# power_supply_module.net
KiCad netlist of a schematic drawn in EAGLE
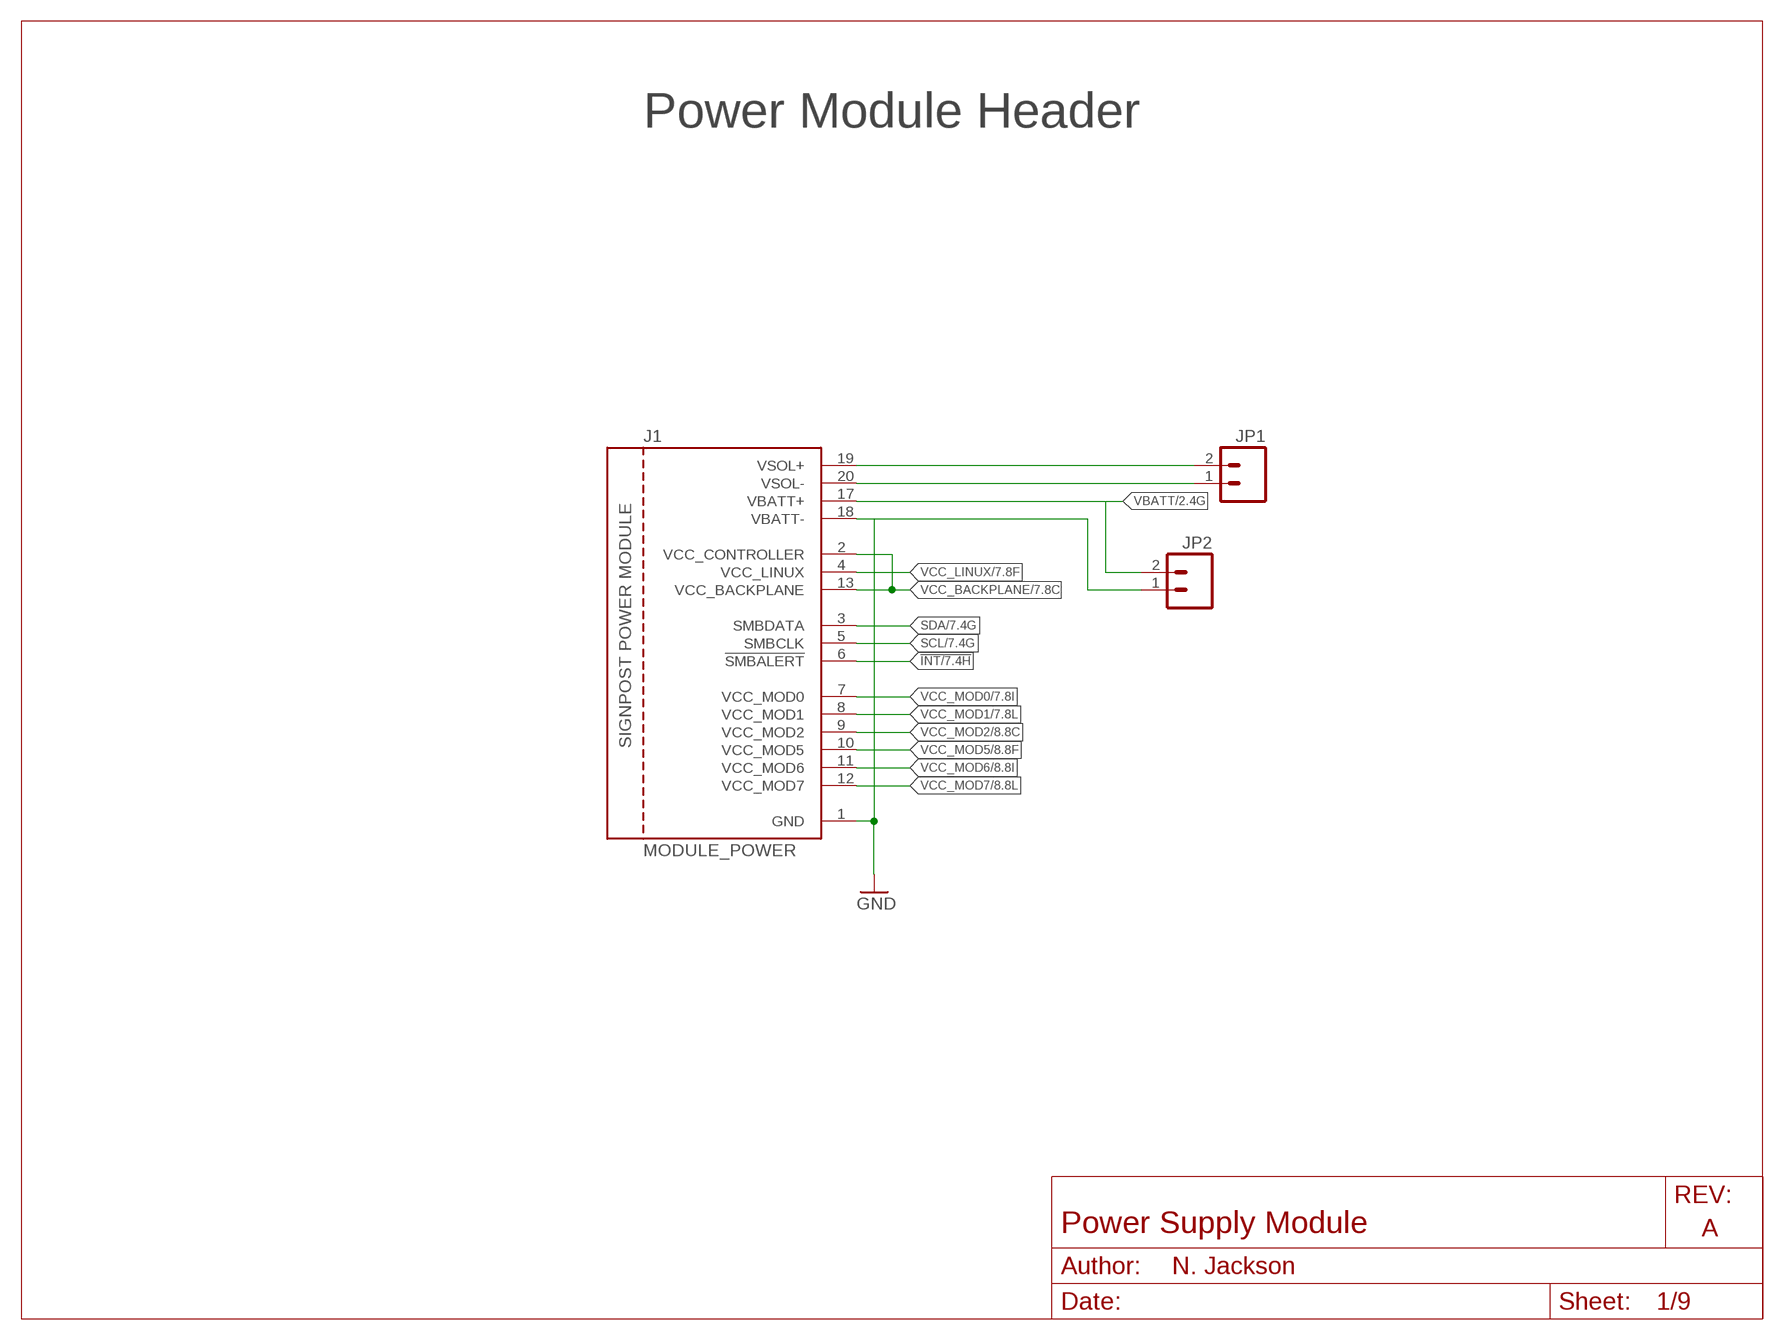
[diagram p0: schematic, sheet 1]
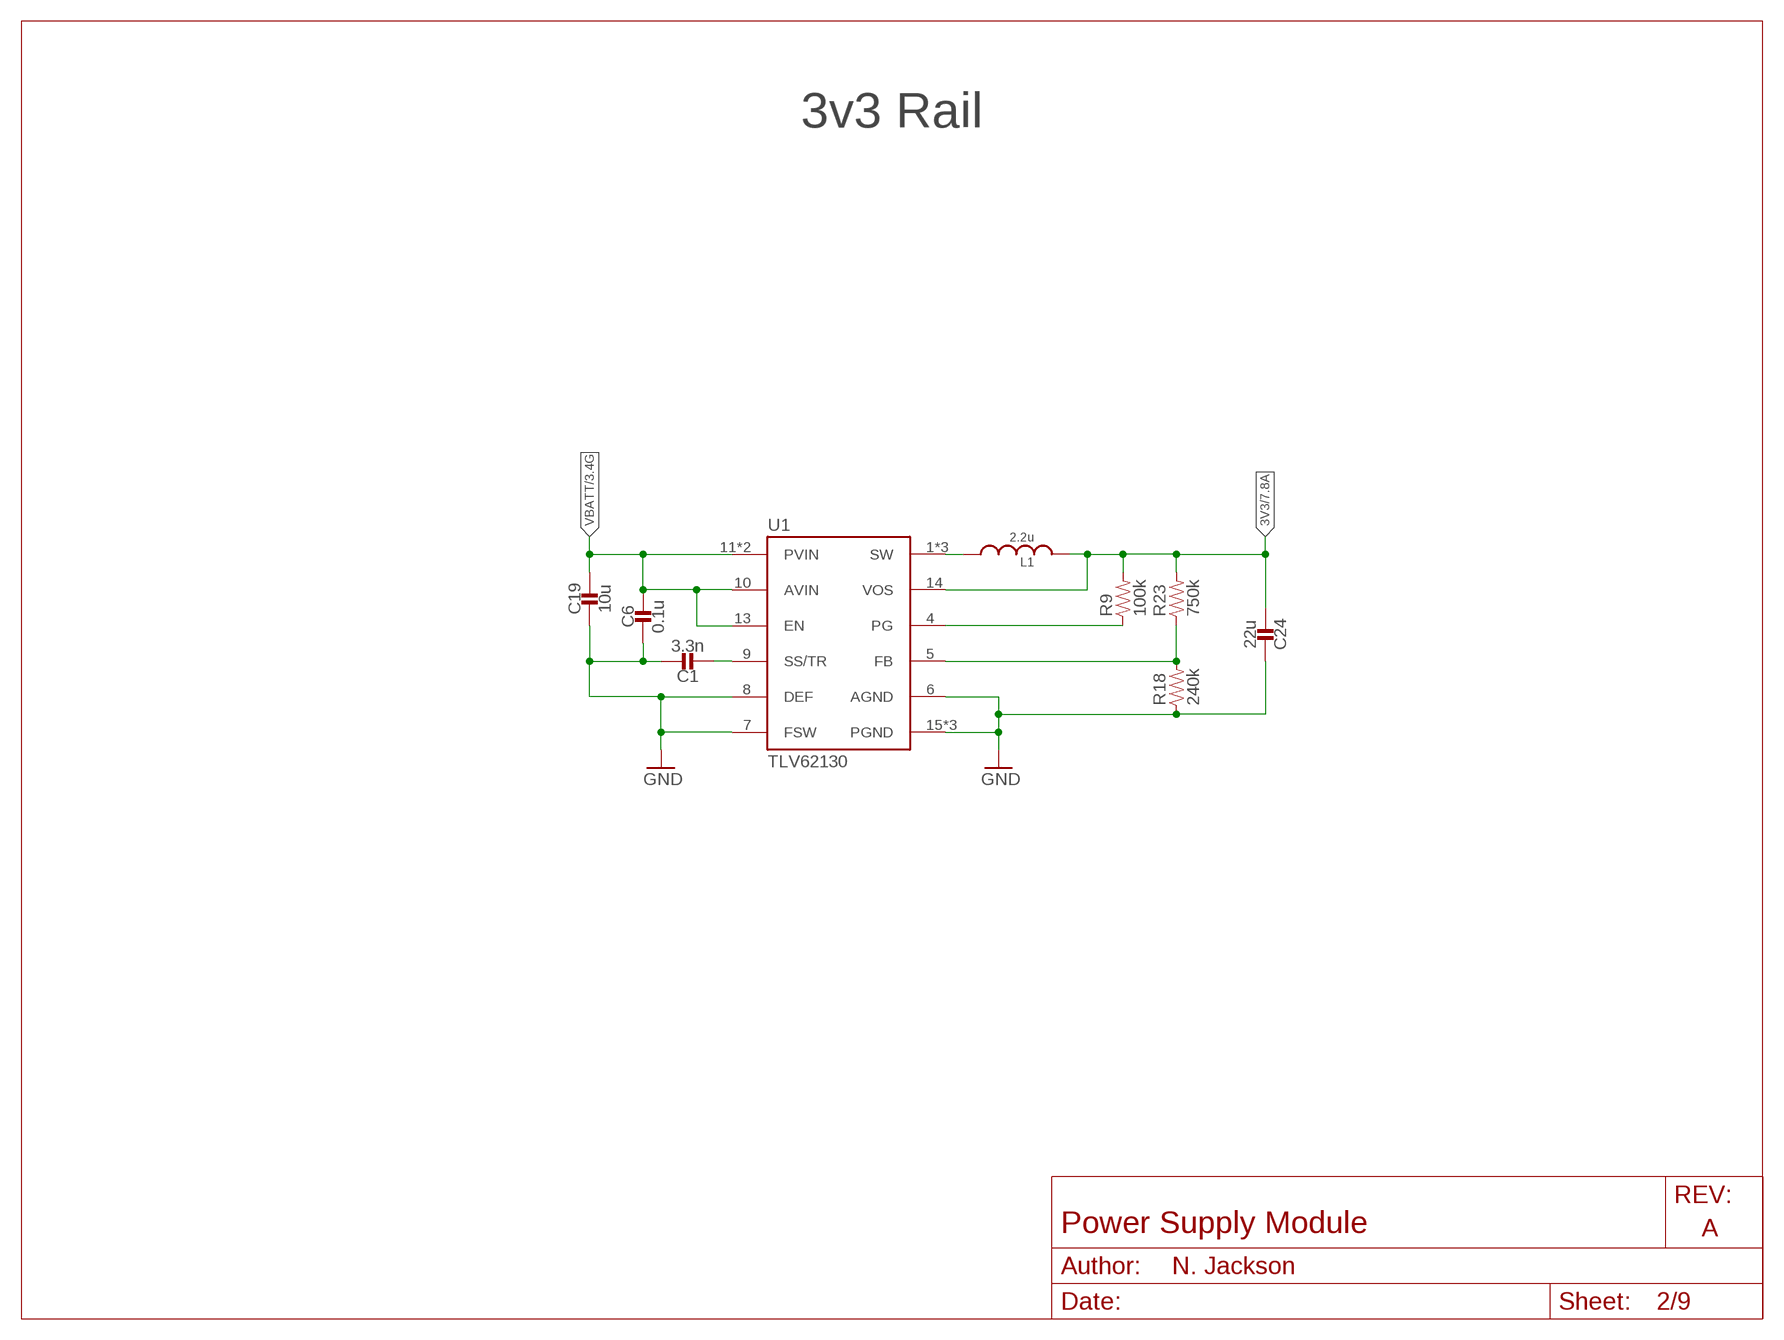
[diagram p1: schematic, sheet 2]
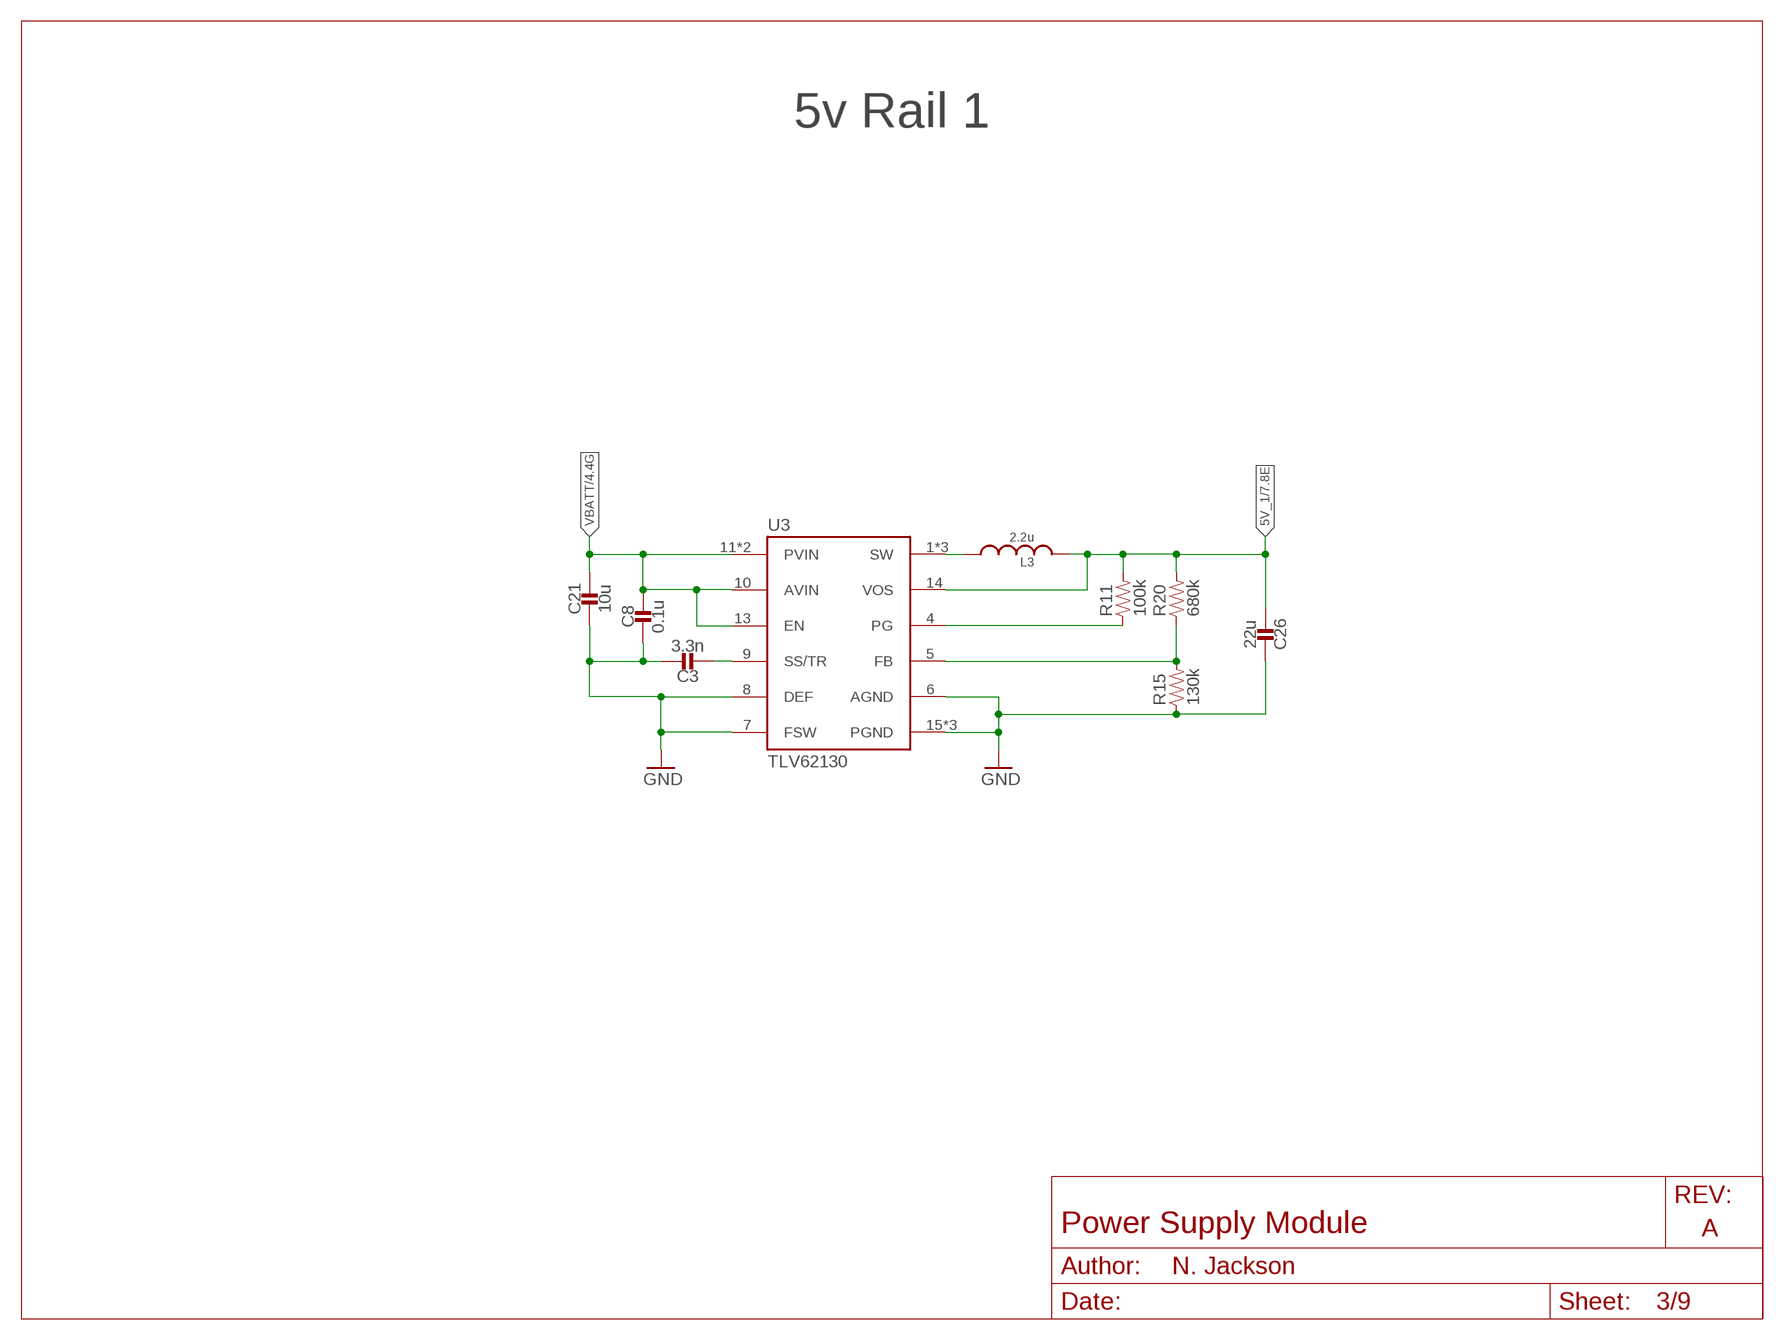
[diagram p2: schematic, sheet 3]
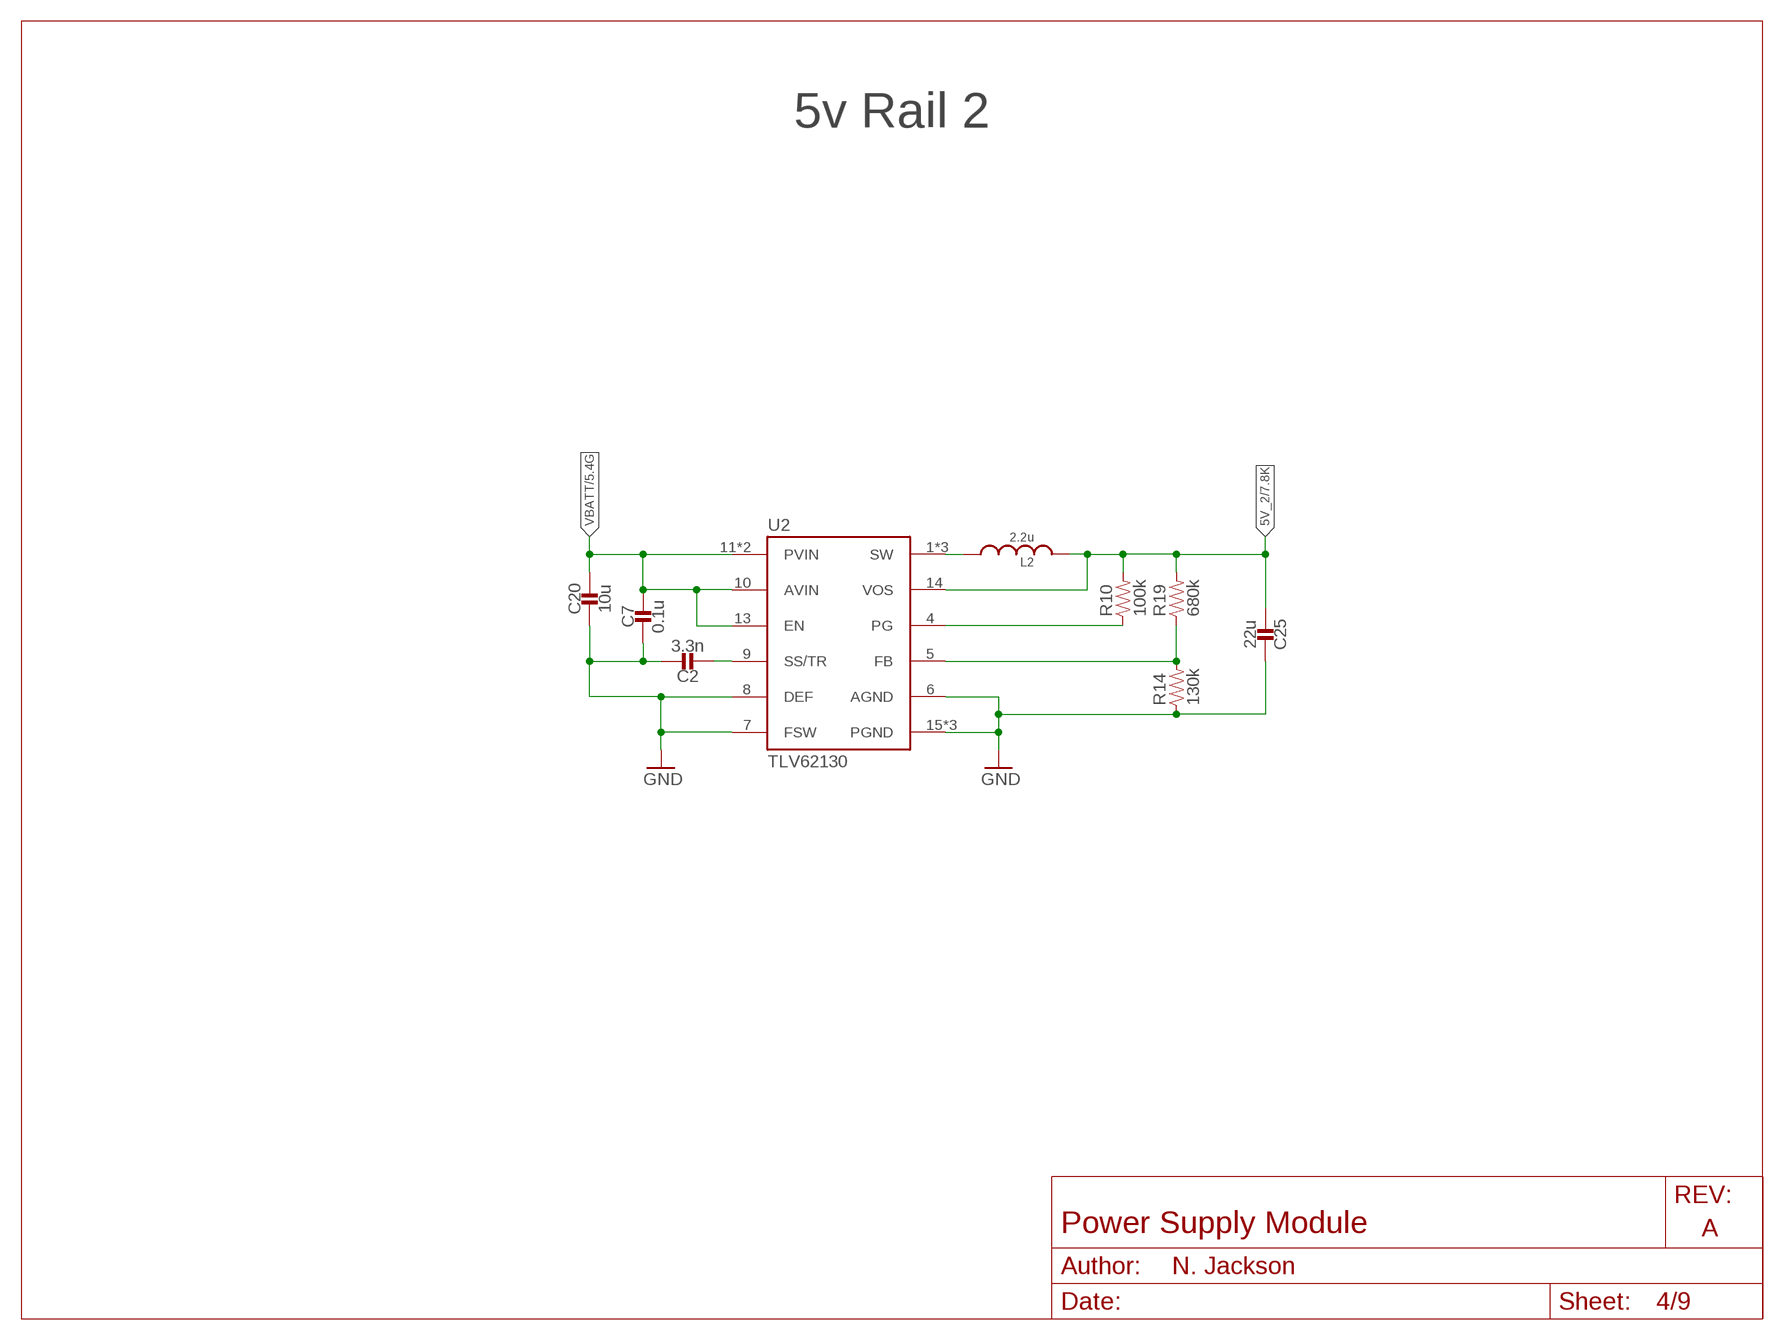
[diagram p3: schematic, sheet 4]
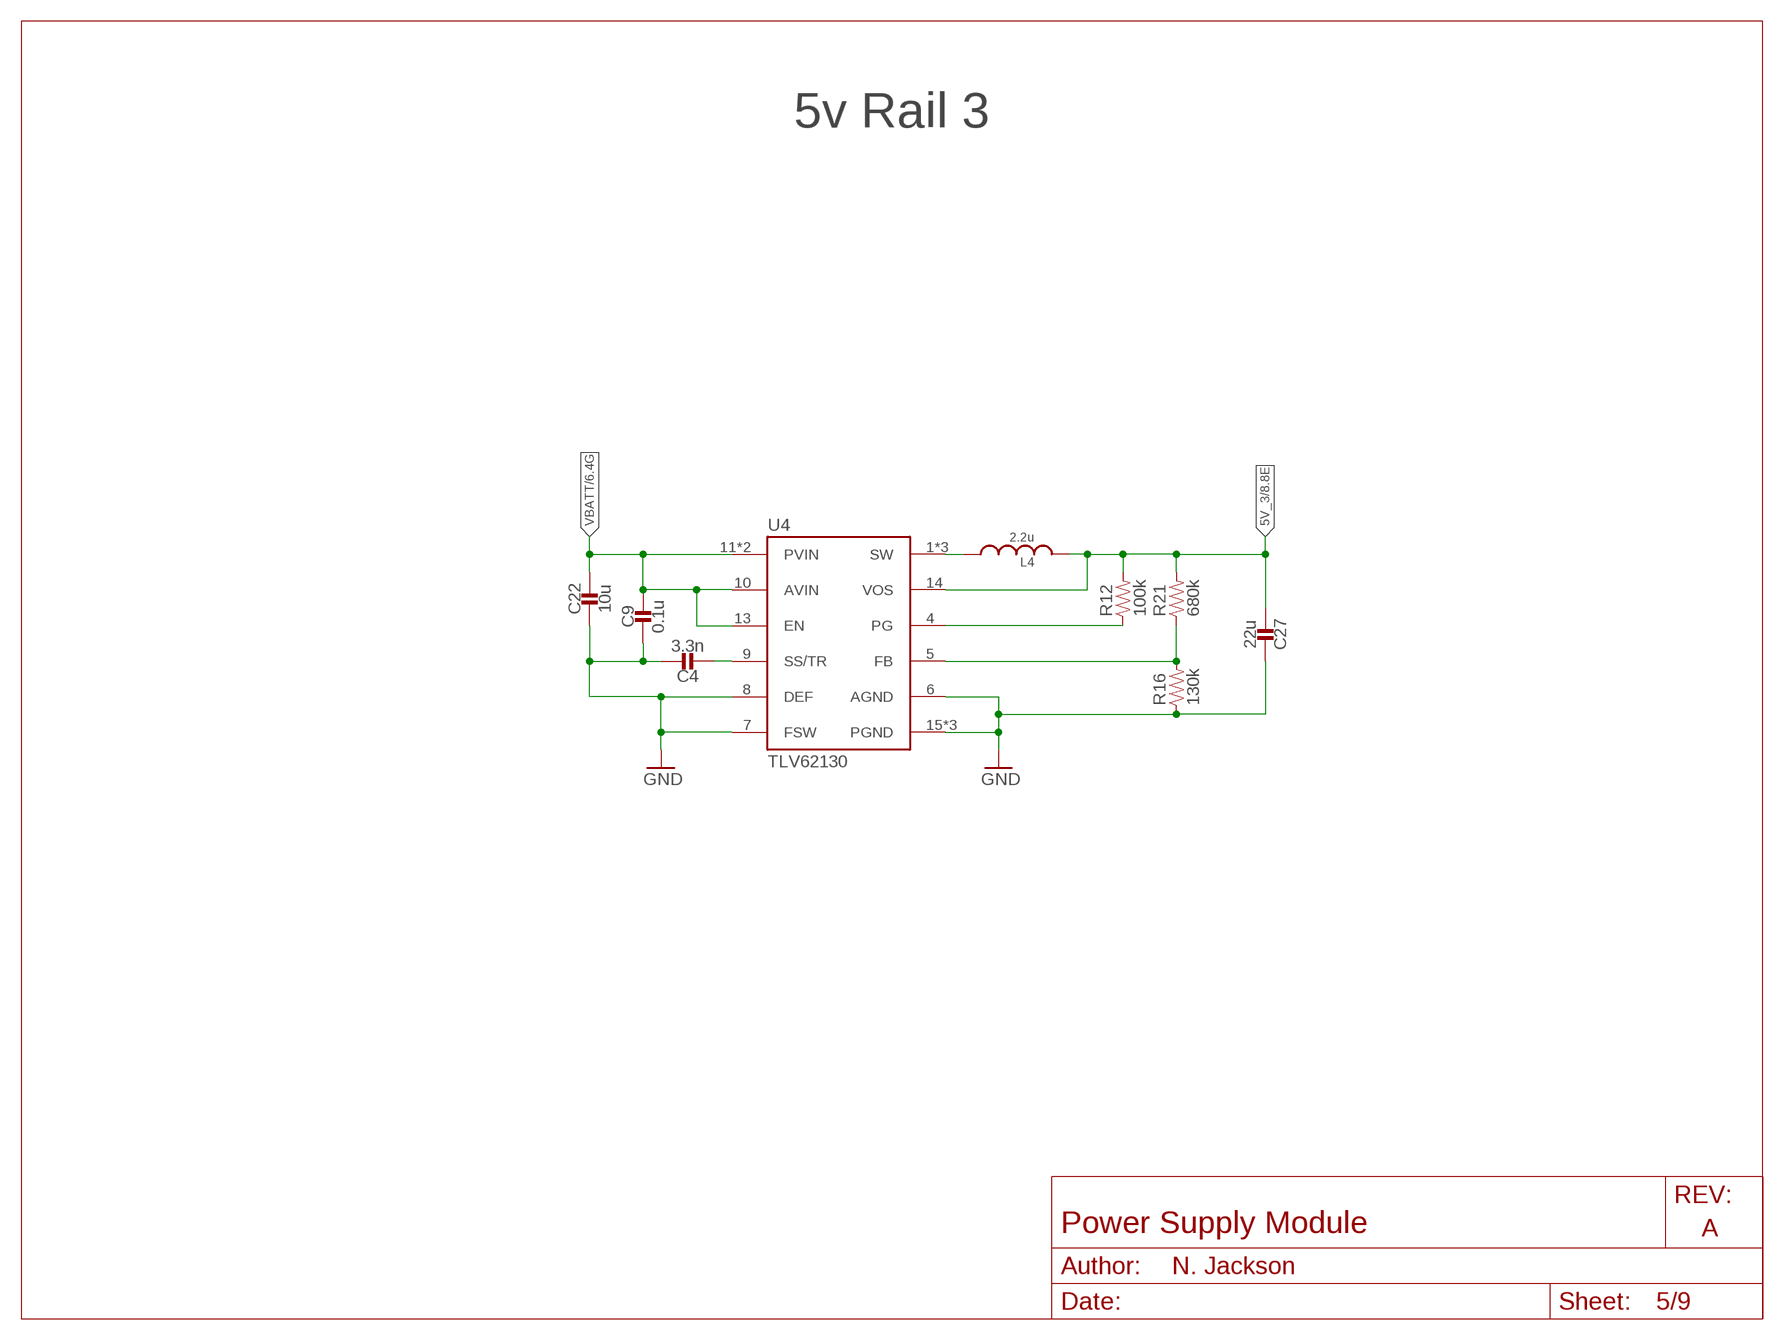
[diagram p4: schematic, sheet 5]
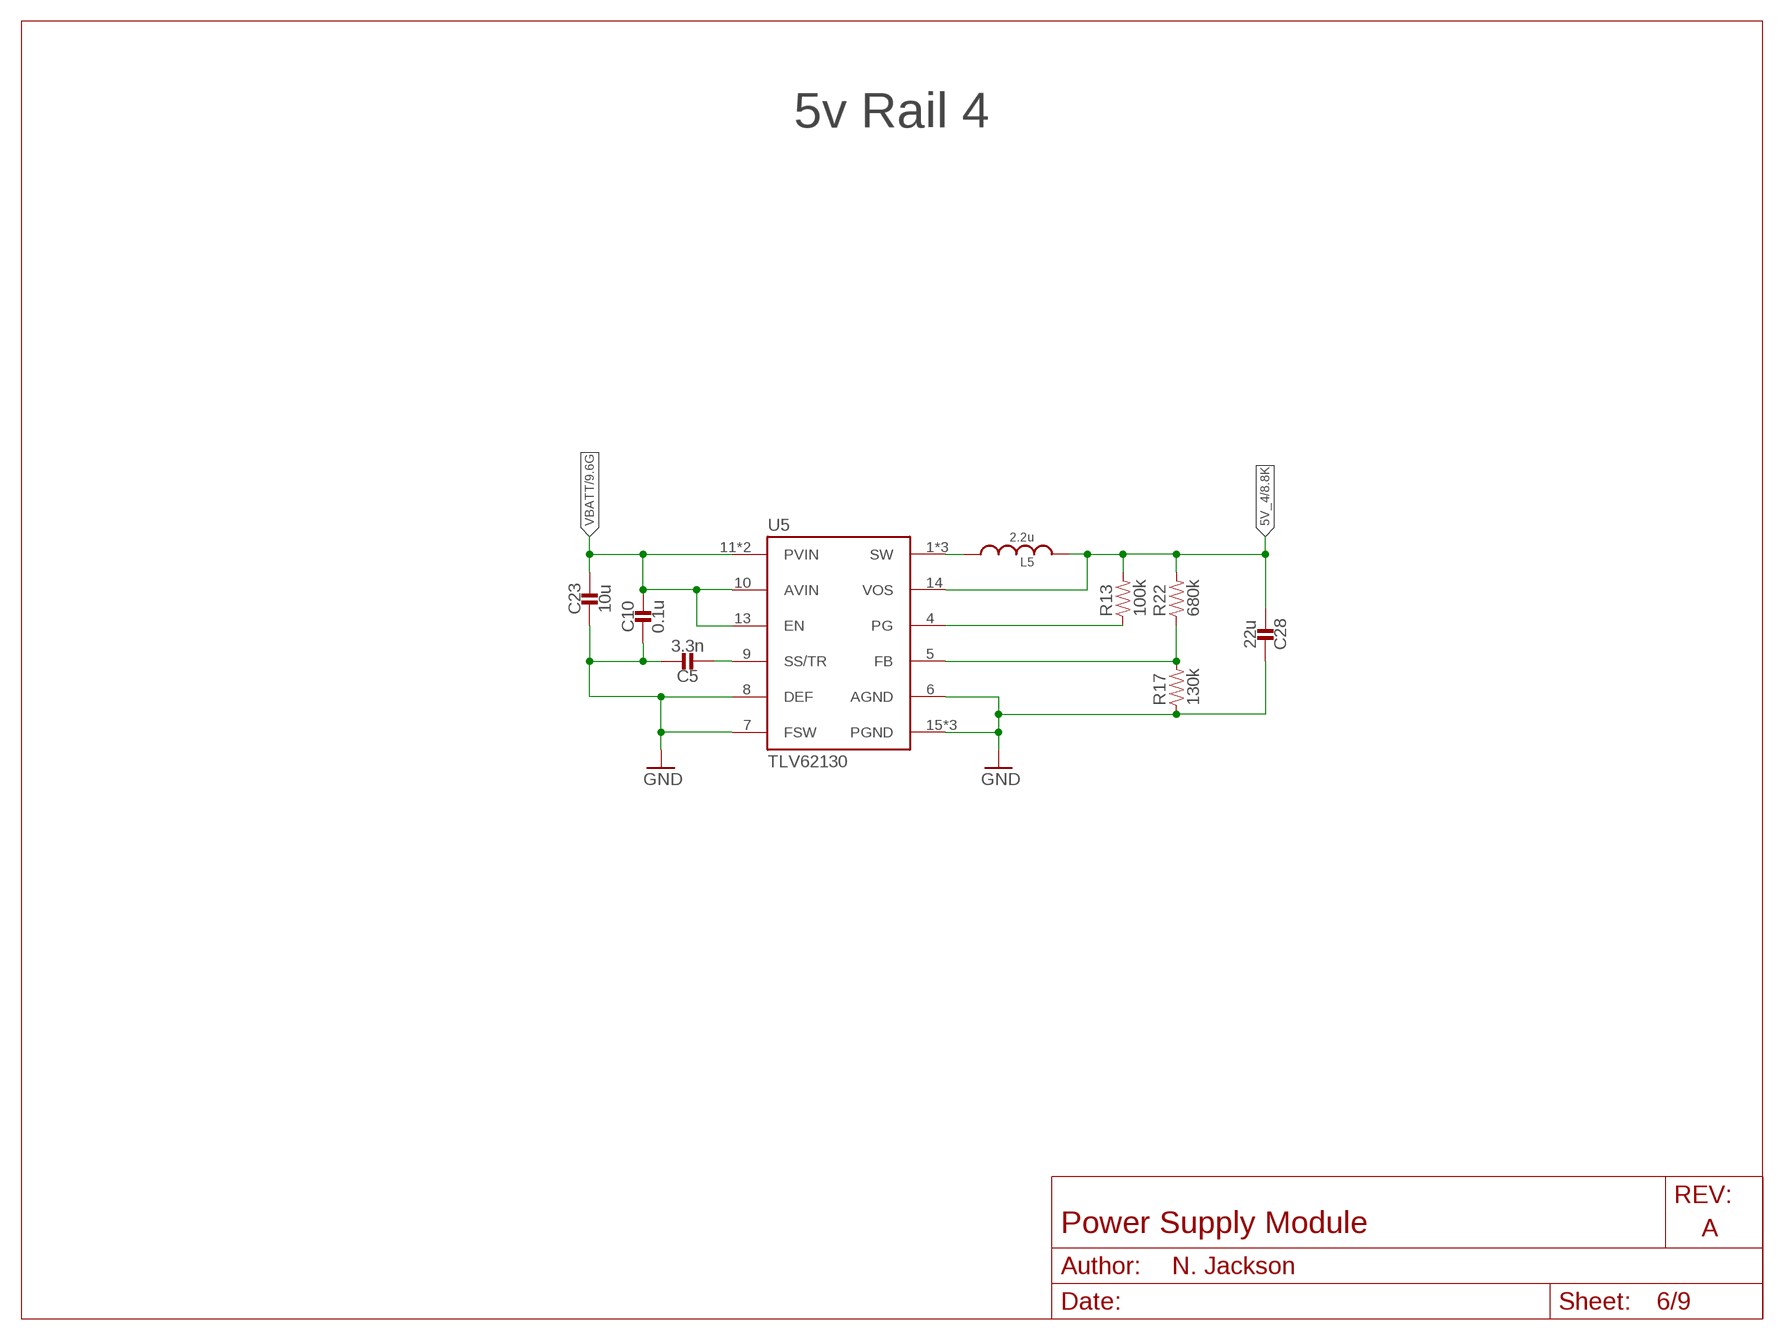
[diagram p5: schematic, sheet 6]
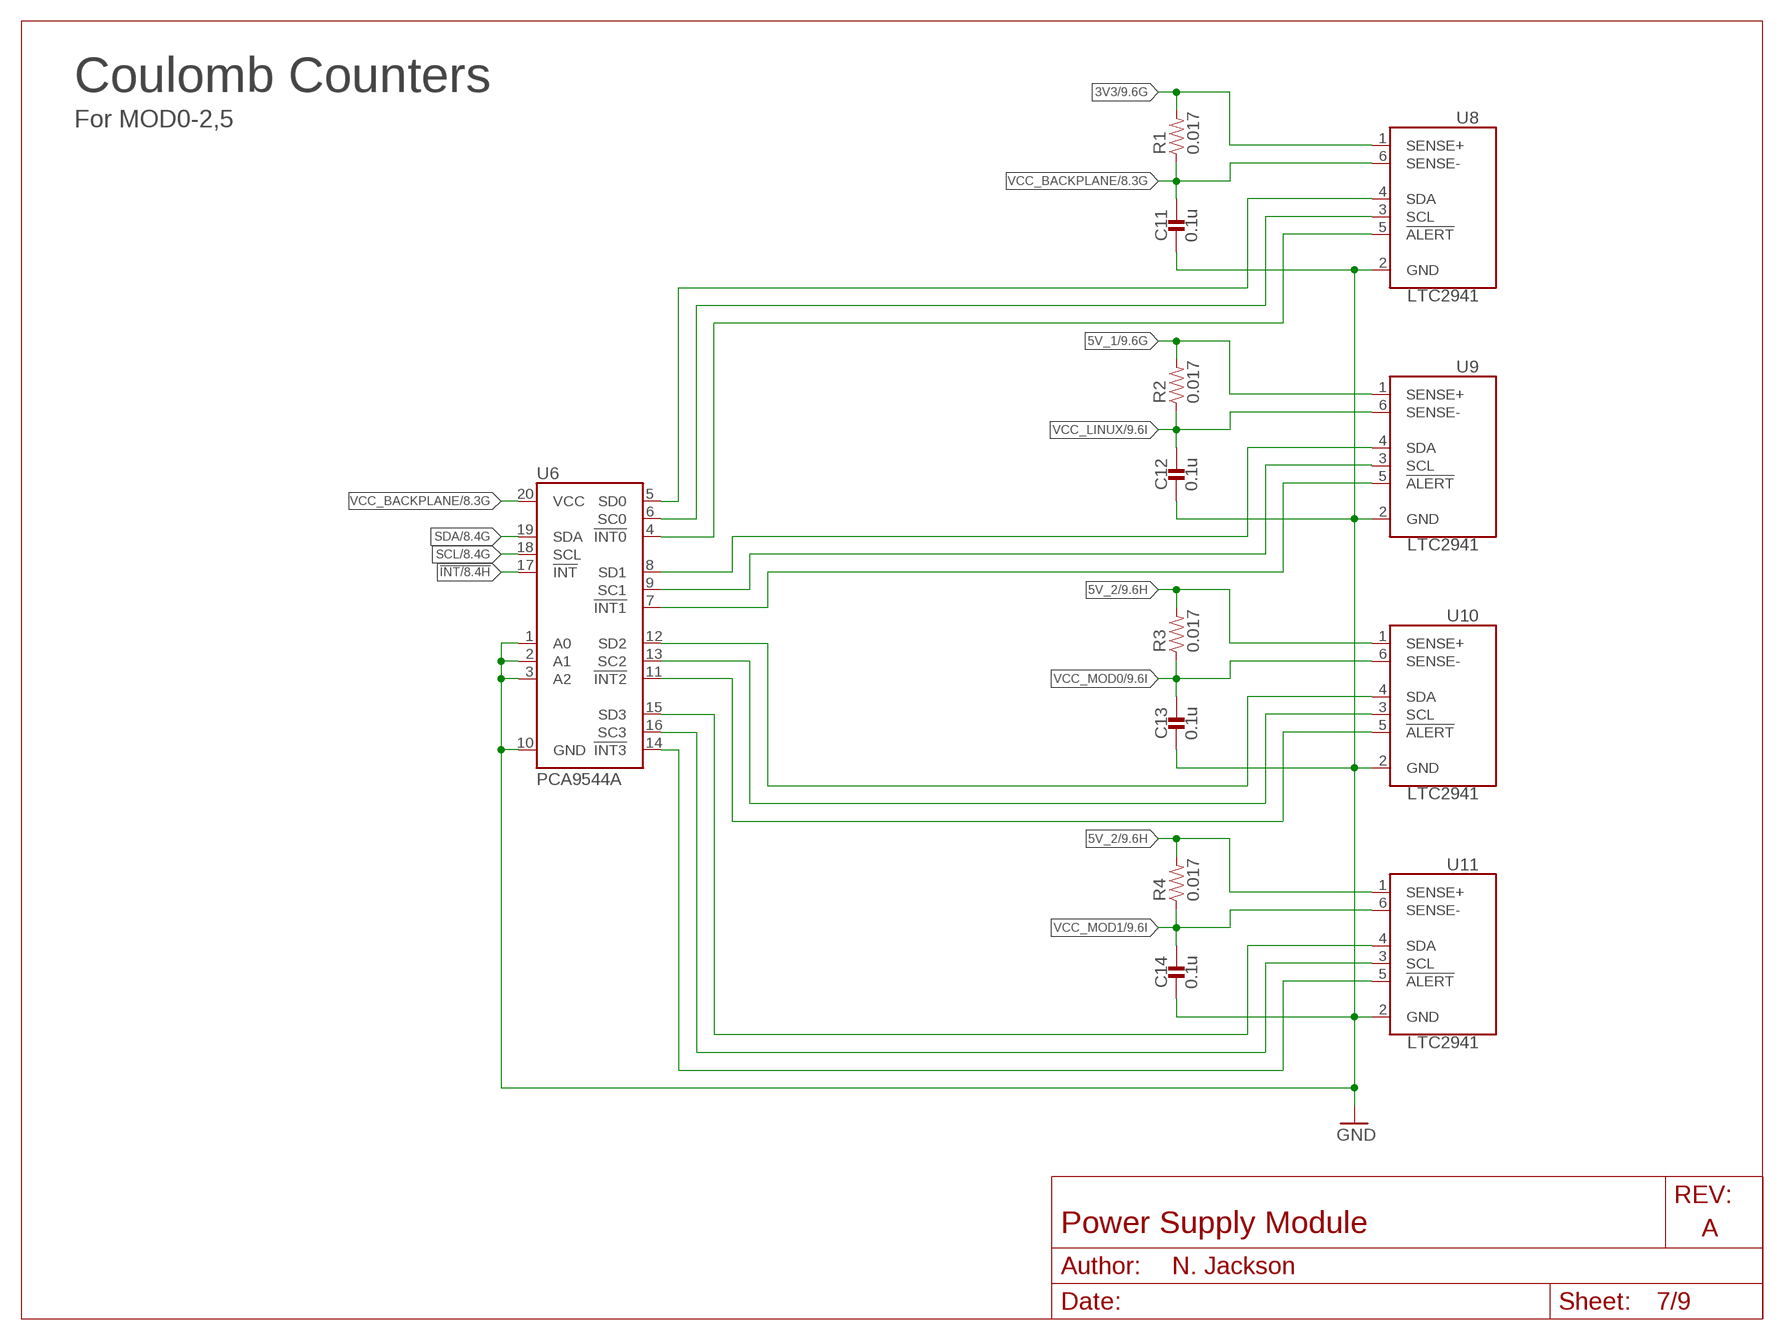
[diagram p6: schematic, sheet 7]
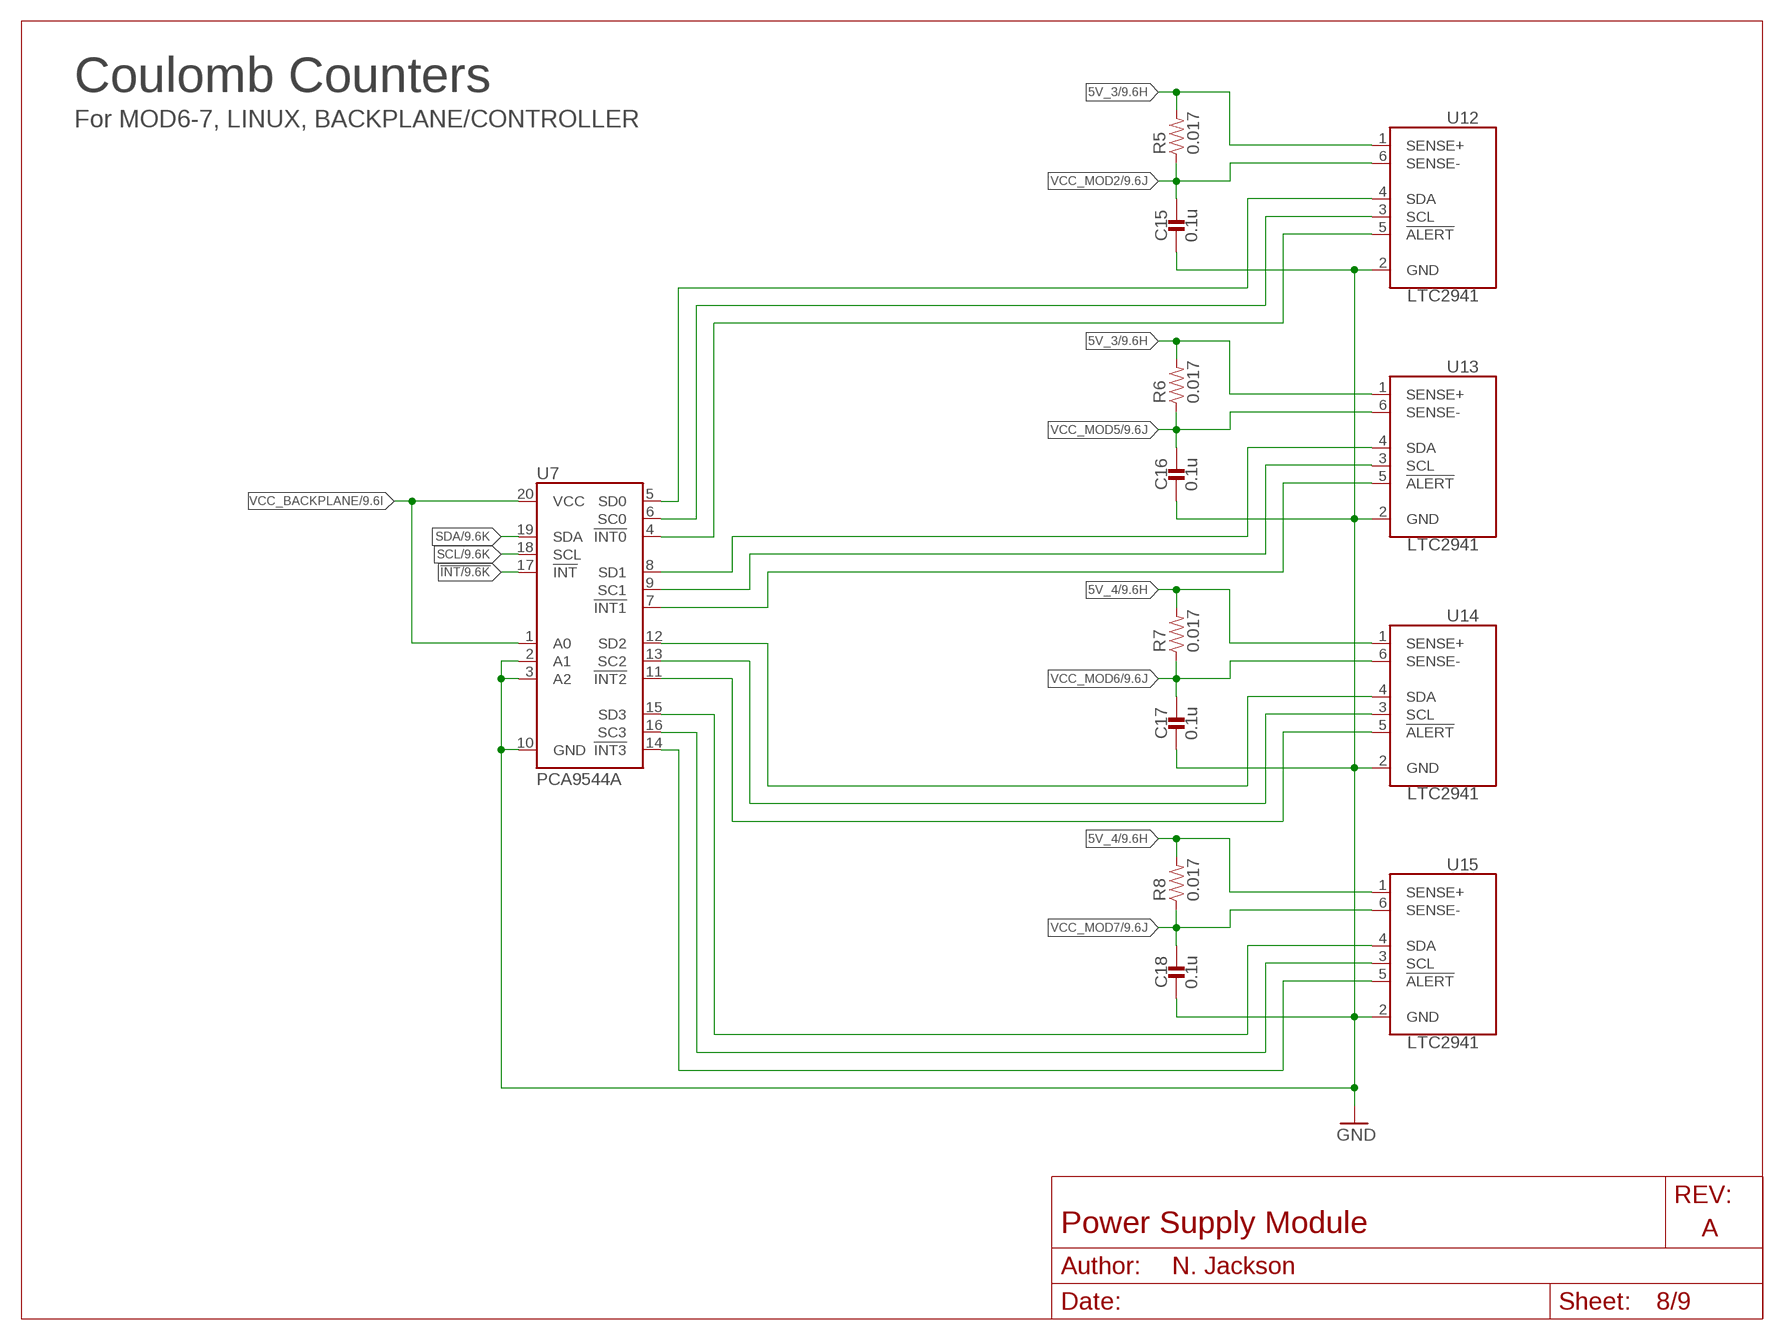
[diagram p7: schematic, sheet 8]
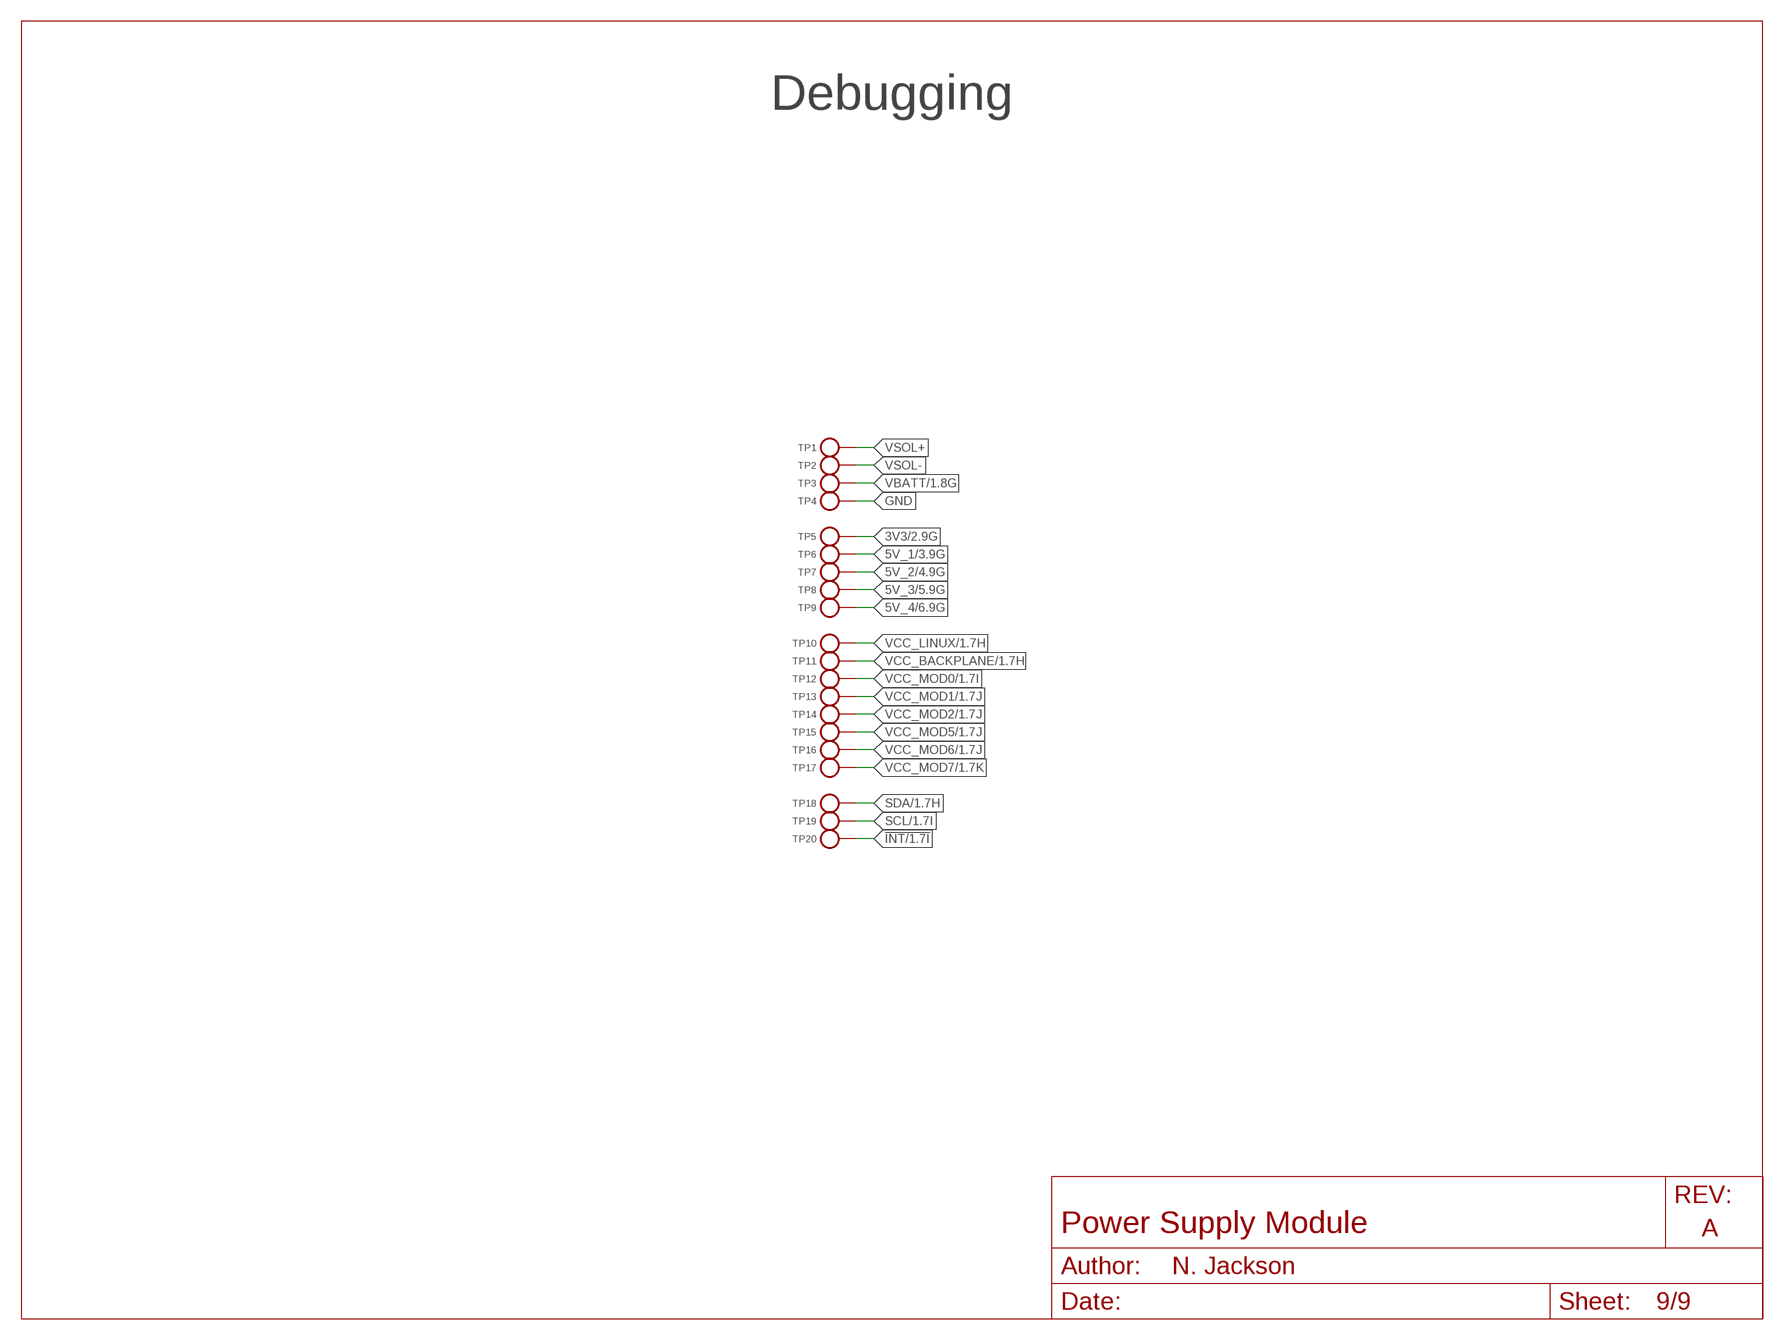
[diagram p8: schematic, sheet 9]

(export (version "E")
  (design (tool "Eeschema 10.0.6"))
  (components
    (comp (ref "C4")
      (value "3.3n")
      (footprint "eagle-import:0402_CAP")
      (libsource (lib "eagle-import") (part "CAPACITOR0402_CAP"))
    )
    (comp (ref "C9")
      (value "0.1u")
      (footprint "eagle-import:0402_CAP")
      (libsource (lib "eagle-import") (part "CAPACITOR0402_CAP"))
    )
    (comp (ref "C22")
      (value "10u")
      (footprint "eagle-import:0805_CAP")
      (libsource (lib "eagle-import") (part "CAPACITOR0805_CAP"))
    )
    (comp (ref "C27")
      (value "22u")
      (footprint "eagle-import:0603_CAP")
      (libsource (lib "eagle-import") (part "CAPACITOR0603_CAP"))
    )
    (comp (ref "L4")
      (value "2.2u")
      (footprint "eagle-import:IHL-1212BZ-11")
      (libsource (lib "eagle-import") (part "INDUCTORIHL"))
    )
    (comp (ref "R12")
      (value "100k")
      (footprint "eagle-import:0402_RES")
      (libsource (lib "eagle-import") (part "RESISTOR0402_RES"))
    )
    (comp (ref "R16")
      (value "130k")
      (footprint "eagle-import:0402_RES")
      (libsource (lib "eagle-import") (part "RESISTOR0402_RES"))
    )
    (comp (ref "R21")
      (value "680k")
      (footprint "eagle-import:0402_RES")
      (libsource (lib "eagle-import") (part "RESISTOR0402_RES"))
    )
    (comp (ref "U4")
      (value "TLV62130")
      (footprint "eagle-import:TQFN-16_3MM")
      (libsource (lib "eagle-import") (part "TLV62130"))
    )
    (comp (ref "C5")
      (value "3.3n")
      (footprint "eagle-import:0402_CAP")
      (libsource (lib "eagle-import") (part "CAPACITOR0402_CAP"))
    )
    (comp (ref "C10")
      (value "0.1u")
      (footprint "eagle-import:0402_CAP")
      (libsource (lib "eagle-import") (part "CAPACITOR0402_CAP"))
    )
    (comp (ref "C23")
      (value "10u")
      (footprint "eagle-import:0805_CAP")
      (libsource (lib "eagle-import") (part "CAPACITOR0805_CAP"))
    )
    (comp (ref "C28")
      (value "22u")
      (footprint "eagle-import:0603_CAP")
      (libsource (lib "eagle-import") (part "CAPACITOR0603_CAP"))
    )
    (comp (ref "L5")
      (value "2.2u")
      (footprint "eagle-import:IHL-1212BZ-11")
      (libsource (lib "eagle-import") (part "INDUCTORIHL"))
    )
    (comp (ref "R13")
      (value "100k")
      (footprint "eagle-import:0402_RES")
      (libsource (lib "eagle-import") (part "RESISTOR0402_RES"))
    )
    (comp (ref "R17")
      (value "130k")
      (footprint "eagle-import:0402_RES")
      (libsource (lib "eagle-import") (part "RESISTOR0402_RES"))
    )
    (comp (ref "R22")
      (value "680k")
      (footprint "eagle-import:0402_RES")
      (libsource (lib "eagle-import") (part "RESISTOR0402_RES"))
    )
    (comp (ref "U5")
      (value "TLV62130")
      (footprint "eagle-import:TQFN-16_3MM")
      (libsource (lib "eagle-import") (part "TLV62130"))
    )
    (comp (ref "TP1")
      (value "TEST_POINT_0.040IN")
      (footprint "eagle-import:TESTPOINT_0.040IN")
      (libsource (lib "eagle-import") (part "TEST_POINT_0.040IN"))
    )
    (comp (ref "TP2")
      (value "TEST_POINT_0.040IN")
      (footprint "eagle-import:TESTPOINT_0.040IN")
      (libsource (lib "eagle-import") (part "TEST_POINT_0.040IN"))
    )
    (comp (ref "TP3")
      (value "TEST_POINT_0.040IN")
      (footprint "eagle-import:TESTPOINT_0.040IN")
      (libsource (lib "eagle-import") (part "TEST_POINT_0.040IN"))
    )
    (comp (ref "TP4")
      (value "TEST_POINT_0.040IN")
      (footprint "eagle-import:TESTPOINT_0.040IN")
      (libsource (lib "eagle-import") (part "TEST_POINT_0.040IN"))
    )
    (comp (ref "TP5")
      (value "TEST_POINT_0.040IN")
      (footprint "eagle-import:TESTPOINT_0.040IN")
      (libsource (lib "eagle-import") (part "TEST_POINT_0.040IN"))
    )
    (comp (ref "TP6")
      (value "TEST_POINT_0.040IN")
      (footprint "eagle-import:TESTPOINT_0.040IN")
      (libsource (lib "eagle-import") (part "TEST_POINT_0.040IN"))
    )
    (comp (ref "TP7")
      (value "TEST_POINT_0.040IN")
      (footprint "eagle-import:TESTPOINT_0.040IN")
      (libsource (lib "eagle-import") (part "TEST_POINT_0.040IN"))
    )
    (comp (ref "TP8")
      (value "TEST_POINT_0.040IN")
      (footprint "eagle-import:TESTPOINT_0.040IN")
      (libsource (lib "eagle-import") (part "TEST_POINT_0.040IN"))
    )
    (comp (ref "TP9")
      (value "TEST_POINT_0.040IN")
      (footprint "eagle-import:TESTPOINT_0.040IN")
      (libsource (lib "eagle-import") (part "TEST_POINT_0.040IN"))
    )
    (comp (ref "TP10")
      (value "TEST_POINT_0.040IN")
      (footprint "eagle-import:TESTPOINT_0.040IN")
      (libsource (lib "eagle-import") (part "TEST_POINT_0.040IN"))
    )
    (comp (ref "TP11")
      (value "TEST_POINT_0.040IN")
      (footprint "eagle-import:TESTPOINT_0.040IN")
      (libsource (lib "eagle-import") (part "TEST_POINT_0.040IN"))
    )
    (comp (ref "TP12")
      (value "TEST_POINT_0.040IN")
      (footprint "eagle-import:TESTPOINT_0.040IN")
      (libsource (lib "eagle-import") (part "TEST_POINT_0.040IN"))
    )
    (comp (ref "TP13")
      (value "TEST_POINT_0.040IN")
      (footprint "eagle-import:TESTPOINT_0.040IN")
      (libsource (lib "eagle-import") (part "TEST_POINT_0.040IN"))
    )
    (comp (ref "TP14")
      (value "TEST_POINT_0.040IN")
      (footprint "eagle-import:TESTPOINT_0.040IN")
      (libsource (lib "eagle-import") (part "TEST_POINT_0.040IN"))
    )
    (comp (ref "TP15")
      (value "TEST_POINT_0.040IN")
      (footprint "eagle-import:TESTPOINT_0.040IN")
      (libsource (lib "eagle-import") (part "TEST_POINT_0.040IN"))
    )
    (comp (ref "TP16")
      (value "TEST_POINT_0.040IN")
      (footprint "eagle-import:TESTPOINT_0.040IN")
      (libsource (lib "eagle-import") (part "TEST_POINT_0.040IN"))
    )
    (comp (ref "TP17")
      (value "TEST_POINT_0.040IN")
      (footprint "eagle-import:TESTPOINT_0.040IN")
      (libsource (lib "eagle-import") (part "TEST_POINT_0.040IN"))
    )
    (comp (ref "TP18")
      (value "TEST_POINT_0.040IN")
      (footprint "eagle-import:TESTPOINT_0.040IN")
      (libsource (lib "eagle-import") (part "TEST_POINT_0.040IN"))
    )
    (comp (ref "TP19")
      (value "TEST_POINT_0.040IN")
      (footprint "eagle-import:TESTPOINT_0.040IN")
      (libsource (lib "eagle-import") (part "TEST_POINT_0.040IN"))
    )
    (comp (ref "TP20")
      (value "TEST_POINT_0.040IN")
      (footprint "eagle-import:TESTPOINT_0.040IN")
      (libsource (lib "eagle-import") (part "TEST_POINT_0.040IN"))
    )
    (comp (ref "C15")
      (value "0.1u")
      (footprint "eagle-import:0402_CAP")
      (libsource (lib "eagle-import") (part "CAPACITOR0402_CAP"))
    )
    (comp (ref "C16")
      (value "0.1u")
      (footprint "eagle-import:0402_CAP")
      (libsource (lib "eagle-import") (part "CAPACITOR0402_CAP"))
    )
    (comp (ref "C17")
      (value "0.1u")
      (footprint "eagle-import:0402_CAP")
      (libsource (lib "eagle-import") (part "CAPACITOR0402_CAP"))
    )
    (comp (ref "C18")
      (value "0.1u")
      (footprint "eagle-import:0402_CAP")
      (libsource (lib "eagle-import") (part "CAPACITOR0402_CAP"))
    )
    (comp (ref "R5")
      (value "0.017")
      (footprint "eagle-import:0805_RES")
      (libsource (lib "eagle-import") (part "RESISTOR0805_RES"))
    )
    (comp (ref "R6")
      (value "0.017")
      (footprint "eagle-import:0805_RES")
      (libsource (lib "eagle-import") (part "RESISTOR0805_RES"))
    )
    (comp (ref "R7")
      (value "0.017")
      (footprint "eagle-import:0805_RES")
      (libsource (lib "eagle-import") (part "RESISTOR0805_RES"))
    )
    (comp (ref "R8")
      (value "0.017")
      (footprint "eagle-import:0805_RES")
      (libsource (lib "eagle-import") (part "RESISTOR0805_RES"))
    )
    (comp (ref "U7")
      (value "PCA9544A")
      (footprint "eagle-import:SO20L")
      (libsource (lib "eagle-import") (part "PCA9544A"))
    )
    (comp (ref "U12")
      (value "LTC2941")
      (footprint "eagle-import:DFN-6-2MMX3MM")
      (libsource (lib "eagle-import") (part "LTC2941"))
    )
    (comp (ref "U13")
      (value "LTC2941")
      (footprint "eagle-import:DFN-6-2MMX3MM")
      (libsource (lib "eagle-import") (part "LTC2941"))
    )
    (comp (ref "U14")
      (value "LTC2941")
      (footprint "eagle-import:DFN-6-2MMX3MM")
      (libsource (lib "eagle-import") (part "LTC2941"))
    )
    (comp (ref "U15")
      (value "LTC2941")
      (footprint "eagle-import:DFN-6-2MMX3MM")
      (libsource (lib "eagle-import") (part "LTC2941"))
    )
    (comp (ref "C11")
      (value "0.1u")
      (footprint "eagle-import:0402_CAP")
      (libsource (lib "eagle-import") (part "CAPACITOR0402_CAP"))
    )
    (comp (ref "C12")
      (value "0.1u")
      (footprint "eagle-import:0402_CAP")
      (libsource (lib "eagle-import") (part "CAPACITOR0402_CAP"))
    )
    (comp (ref "C13")
      (value "0.1u")
      (footprint "eagle-import:0402_CAP")
      (libsource (lib "eagle-import") (part "CAPACITOR0402_CAP"))
    )
    (comp (ref "C14")
      (value "0.1u")
      (footprint "eagle-import:0402_CAP")
      (libsource (lib "eagle-import") (part "CAPACITOR0402_CAP"))
    )
    (comp (ref "R1")
      (value "0.017")
      (footprint "eagle-import:0805_RES")
      (libsource (lib "eagle-import") (part "RESISTOR0805_RES"))
    )
    (comp (ref "R2")
      (value "0.017")
      (footprint "eagle-import:0805_RES")
      (libsource (lib "eagle-import") (part "RESISTOR0805_RES"))
    )
    (comp (ref "R3")
      (value "0.017")
      (footprint "eagle-import:0805_RES")
      (libsource (lib "eagle-import") (part "RESISTOR0805_RES"))
    )
    (comp (ref "R4")
      (value "0.017")
      (footprint "eagle-import:0805_RES")
      (libsource (lib "eagle-import") (part "RESISTOR0805_RES"))
    )
    (comp (ref "U6")
      (value "PCA9544A")
      (footprint "eagle-import:SO20L")
      (libsource (lib "eagle-import") (part "PCA9544A"))
    )
    (comp (ref "U8")
      (value "LTC2941")
      (footprint "eagle-import:DFN-6-2MMX3MM")
      (libsource (lib "eagle-import") (part "LTC2941"))
    )
    (comp (ref "U9")
      (value "LTC2941")
      (footprint "eagle-import:DFN-6-2MMX3MM")
      (libsource (lib "eagle-import") (part "LTC2941"))
    )
    (comp (ref "U10")
      (value "LTC2941")
      (footprint "eagle-import:DFN-6-2MMX3MM")
      (libsource (lib "eagle-import") (part "LTC2941"))
    )
    (comp (ref "U11")
      (value "LTC2941")
      (footprint "eagle-import:DFN-6-2MMX3MM")
      (libsource (lib "eagle-import") (part "LTC2941"))
    )
    (comp (ref "C2")
      (value "3.3n")
      (footprint "eagle-import:0402_CAP")
      (libsource (lib "eagle-import") (part "CAPACITOR0402_CAP"))
    )
    (comp (ref "C7")
      (value "0.1u")
      (footprint "eagle-import:0402_CAP")
      (libsource (lib "eagle-import") (part "CAPACITOR0402_CAP"))
    )
    (comp (ref "C20")
      (value "10u")
      (footprint "eagle-import:0805_CAP")
      (libsource (lib "eagle-import") (part "CAPACITOR0805_CAP"))
    )
    (comp (ref "C25")
      (value "22u")
      (footprint "eagle-import:0603_CAP")
      (libsource (lib "eagle-import") (part "CAPACITOR0603_CAP"))
    )
    (comp (ref "L2")
      (value "2.2u")
      (footprint "eagle-import:IHL-1212BZ-11")
      (libsource (lib "eagle-import") (part "INDUCTORIHL"))
    )
    (comp (ref "R10")
      (value "100k")
      (footprint "eagle-import:0402_RES")
      (libsource (lib "eagle-import") (part "RESISTOR0402_RES"))
    )
    (comp (ref "R14")
      (value "130k")
      (footprint "eagle-import:0402_RES")
      (libsource (lib "eagle-import") (part "RESISTOR0402_RES"))
    )
    (comp (ref "R19")
      (value "680k")
      (footprint "eagle-import:0402_RES")
      (libsource (lib "eagle-import") (part "RESISTOR0402_RES"))
    )
    (comp (ref "U2")
      (value "TLV62130")
      (footprint "eagle-import:TQFN-16_3MM")
      (libsource (lib "eagle-import") (part "TLV62130"))
    )
    (comp (ref "C1")
      (value "3.3n")
      (footprint "eagle-import:0402_CAP")
      (libsource (lib "eagle-import") (part "CAPACITOR0402_CAP"))
    )
    (comp (ref "C6")
      (value "0.1u")
      (footprint "eagle-import:0402_CAP")
      (libsource (lib "eagle-import") (part "CAPACITOR0402_CAP"))
    )
    (comp (ref "C19")
      (value "10u")
      (footprint "eagle-import:0805_CAP")
      (libsource (lib "eagle-import") (part "CAPACITOR0805_CAP"))
    )
    (comp (ref "C24")
      (value "22u")
      (footprint "eagle-import:0603_CAP")
      (libsource (lib "eagle-import") (part "CAPACITOR0603_CAP"))
    )
    (comp (ref "L1")
      (value "2.2u")
      (footprint "eagle-import:IHL-1212BZ-11")
      (libsource (lib "eagle-import") (part "INDUCTORIHL"))
    )
    (comp (ref "R9")
      (value "100k")
      (footprint "eagle-import:0402_RES")
      (libsource (lib "eagle-import") (part "RESISTOR0402_RES"))
    )
    (comp (ref "R18")
      (value "240k")
      (footprint "eagle-import:0402_RES")
      (libsource (lib "eagle-import") (part "RESISTOR0402_RES"))
    )
    (comp (ref "R23")
      (value "750k")
      (footprint "eagle-import:0402_RES")
      (libsource (lib "eagle-import") (part "RESISTOR0402_RES"))
    )
    (comp (ref "U1")
      (value "TLV62130")
      (footprint "eagle-import:TQFN-16_3MM")
      (libsource (lib "eagle-import") (part "TLV62130"))
    )
    (comp (ref "C3")
      (value "3.3n")
      (footprint "eagle-import:0402_CAP")
      (libsource (lib "eagle-import") (part "CAPACITOR0402_CAP"))
    )
    (comp (ref "C8")
      (value "0.1u")
      (footprint "eagle-import:0402_CAP")
      (libsource (lib "eagle-import") (part "CAPACITOR0402_CAP"))
    )
    (comp (ref "C21")
      (value "10u")
      (footprint "eagle-import:0805_CAP")
      (libsource (lib "eagle-import") (part "CAPACITOR0805_CAP"))
    )
    (comp (ref "C26")
      (value "22u")
      (footprint "eagle-import:0603_CAP")
      (libsource (lib "eagle-import") (part "CAPACITOR0603_CAP"))
    )
    (comp (ref "L3")
      (value "2.2u")
      (footprint "eagle-import:IHL-1212BZ-11")
      (libsource (lib "eagle-import") (part "INDUCTORIHL"))
    )
    (comp (ref "R11")
      (value "100k")
      (footprint "eagle-import:0402_RES")
      (libsource (lib "eagle-import") (part "RESISTOR0402_RES"))
    )
    (comp (ref "R15")
      (value "130k")
      (footprint "eagle-import:0402_RES")
      (libsource (lib "eagle-import") (part "RESISTOR0402_RES"))
    )
    (comp (ref "R20")
      (value "680k")
      (footprint "eagle-import:0402_RES")
      (libsource (lib "eagle-import") (part "RESISTOR0402_RES"))
    )
    (comp (ref "U3")
      (value "TLV62130")
      (footprint "eagle-import:TQFN-16_3MM")
      (libsource (lib "eagle-import") (part "TLV62130"))
    )
    (comp (ref "J1")
      (value "MODULE_POWER")
      (footprint "eagle-import:MODULE_POWER")
      (libsource (lib "eagle-import") (part "MODULE_POWER"))
    )
    (comp (ref "JP1")
      (value "M02PTH")
      (footprint "eagle-import:1X02")
      (libsource (lib "eagle-import") (part "M02PTH"))
    )
    (comp (ref "JP2")
      (value "M02PTH")
      (footprint "eagle-import:1X02")
      (libsource (lib "eagle-import") (part "M02PTH"))
    )
  )
  (nets
    (net (code "1") (name "3V3") (class "Default")
      (node (ref "C24") (pin "2") (pinfunction "2_2") (pintype "bidirectional"))
      (node (ref "L1") (pin "P$2") (pinfunction "2_P$2") (pintype "bidirectional"))
      (node (ref "R1") (pin "2") (pinfunction "2_2") (pintype "passive"))
      (node (ref "R23") (pin "2") (pinfunction "2_2") (pintype "passive"))
      (node (ref "R9") (pin "2") (pinfunction "2_2") (pintype "passive"))
      (node (ref "TP5") (pin "TESTPOINT") (pinfunction "TESTPOINT_TESTPOINT") (pintype "bidirectional"))
      (node (ref "U1") (pin "14") (pinfunction "VOS_14") (pintype "bidirectional"))
      (node (ref "U8") (pin "1") (pinfunction "SENSE+_1") (pintype "open_collector"))
    )
    (net (code "2") (name "5V_1") (class "Default")
      (node (ref "C26") (pin "2") (pinfunction "2_2") (pintype "bidirectional"))
      (node (ref "L3") (pin "P$2") (pinfunction "2_P$2") (pintype "bidirectional"))
      (node (ref "R11") (pin "2") (pinfunction "2_2") (pintype "passive"))
      (node (ref "R2") (pin "2") (pinfunction "2_2") (pintype "passive"))
      (node (ref "R20") (pin "2") (pinfunction "2_2") (pintype "passive"))
      (node (ref "TP6") (pin "TESTPOINT") (pinfunction "TESTPOINT_TESTPOINT") (pintype "bidirectional"))
      (node (ref "U3") (pin "14") (pinfunction "VOS_14") (pintype "bidirectional"))
      (node (ref "U9") (pin "1") (pinfunction "SENSE+_1") (pintype "open_collector"))
    )
    (net (code "3") (name "5V_2") (class "Default")
      (node (ref "C25") (pin "2") (pinfunction "2_2") (pintype "bidirectional"))
      (node (ref "L2") (pin "P$2") (pinfunction "2_P$2") (pintype "bidirectional"))
      (node (ref "R10") (pin "2") (pinfunction "2_2") (pintype "passive"))
      (node (ref "R19") (pin "2") (pinfunction "2_2") (pintype "passive"))
      (node (ref "R3") (pin "2") (pinfunction "2_2") (pintype "passive"))
      (node (ref "R4") (pin "2") (pinfunction "2_2") (pintype "passive"))
      (node (ref "TP7") (pin "TESTPOINT") (pinfunction "TESTPOINT_TESTPOINT") (pintype "bidirectional"))
      (node (ref "U10") (pin "1") (pinfunction "SENSE+_1") (pintype "open_collector"))
      (node (ref "U11") (pin "1") (pinfunction "SENSE+_1") (pintype "open_collector"))
      (node (ref "U2") (pin "14") (pinfunction "VOS_14") (pintype "bidirectional"))
    )
    (net (code "4") (name "5V_3") (class "Default")
      (node (ref "C27") (pin "2") (pinfunction "2_2") (pintype "bidirectional"))
      (node (ref "L4") (pin "P$2") (pinfunction "2_P$2") (pintype "bidirectional"))
      (node (ref "R12") (pin "2") (pinfunction "2_2") (pintype "passive"))
      (node (ref "R21") (pin "2") (pinfunction "2_2") (pintype "passive"))
      (node (ref "R5") (pin "2") (pinfunction "2_2") (pintype "passive"))
      (node (ref "R6") (pin "2") (pinfunction "2_2") (pintype "passive"))
      (node (ref "TP8") (pin "TESTPOINT") (pinfunction "TESTPOINT_TESTPOINT") (pintype "bidirectional"))
      (node (ref "U12") (pin "1") (pinfunction "SENSE+_1") (pintype "open_collector"))
      (node (ref "U13") (pin "1") (pinfunction "SENSE+_1") (pintype "open_collector"))
      (node (ref "U4") (pin "14") (pinfunction "VOS_14") (pintype "bidirectional"))
    )
    (net (code "5") (name "5V_4") (class "Default")
      (node (ref "C28") (pin "2") (pinfunction "2_2") (pintype "bidirectional"))
      (node (ref "L5") (pin "P$2") (pinfunction "2_P$2") (pintype "bidirectional"))
      (node (ref "R13") (pin "2") (pinfunction "2_2") (pintype "passive"))
      (node (ref "R22") (pin "2") (pinfunction "2_2") (pintype "passive"))
      (node (ref "R7") (pin "2") (pinfunction "2_2") (pintype "passive"))
      (node (ref "R8") (pin "2") (pinfunction "2_2") (pintype "passive"))
      (node (ref "TP9") (pin "TESTPOINT") (pinfunction "TESTPOINT_TESTPOINT") (pintype "bidirectional"))
      (node (ref "U14") (pin "1") (pinfunction "SENSE+_1") (pintype "open_collector"))
      (node (ref "U15") (pin "1") (pinfunction "SENSE+_1") (pintype "open_collector"))
      (node (ref "U5") (pin "14") (pinfunction "VOS_14") (pintype "bidirectional"))
    )
    (net (code "6") (name "GND") (class "Default")
      (node (ref "C1") (pin "1") (pinfunction "1_1") (pintype "bidirectional"))
      (node (ref "C10") (pin "2") (pinfunction "2_2") (pintype "bidirectional"))
      (node (ref "C11") (pin "2") (pinfunction "2_2") (pintype "bidirectional"))
      (node (ref "C12") (pin "2") (pinfunction "2_2") (pintype "bidirectional"))
      (node (ref "C13") (pin "2") (pinfunction "2_2") (pintype "bidirectional"))
      (node (ref "C14") (pin "2") (pinfunction "2_2") (pintype "bidirectional"))
      (node (ref "C15") (pin "2") (pinfunction "2_2") (pintype "bidirectional"))
      (node (ref "C16") (pin "2") (pinfunction "2_2") (pintype "bidirectional"))
      (node (ref "C17") (pin "2") (pinfunction "2_2") (pintype "bidirectional"))
      (node (ref "C18") (pin "2") (pinfunction "2_2") (pintype "bidirectional"))
      (node (ref "C19") (pin "P$2") (pinfunction "2_P$2") (pintype "bidirectional"))
      (node (ref "C2") (pin "1") (pinfunction "1_1") (pintype "bidirectional"))
      (node (ref "C20") (pin "P$2") (pinfunction "2_P$2") (pintype "bidirectional"))
      (node (ref "C21") (pin "P$2") (pinfunction "2_P$2") (pintype "bidirectional"))
      (node (ref "C22") (pin "P$2") (pinfunction "2_P$2") (pintype "bidirectional"))
      (node (ref "C23") (pin "P$2") (pinfunction "2_P$2") (pintype "bidirectional"))
      (node (ref "C24") (pin "1") (pinfunction "1_1") (pintype "bidirectional"))
      (node (ref "C25") (pin "1") (pinfunction "1_1") (pintype "bidirectional"))
      (node (ref "C26") (pin "1") (pinfunction "1_1") (pintype "bidirectional"))
      (node (ref "C27") (pin "1") (pinfunction "1_1") (pintype "bidirectional"))
      (node (ref "C28") (pin "1") (pinfunction "1_1") (pintype "bidirectional"))
      (node (ref "C3") (pin "1") (pinfunction "1_1") (pintype "bidirectional"))
      (node (ref "C4") (pin "1") (pinfunction "1_1") (pintype "bidirectional"))
      (node (ref "C5") (pin "1") (pinfunction "1_1") (pintype "bidirectional"))
      (node (ref "C6") (pin "2") (pinfunction "2_2") (pintype "bidirectional"))
      (node (ref "C7") (pin "2") (pinfunction "2_2") (pintype "bidirectional"))
      (node (ref "C8") (pin "2") (pinfunction "2_2") (pintype "bidirectional"))
      (node (ref "C9") (pin "2") (pinfunction "2_2") (pintype "bidirectional"))
      (node (ref "J1") (pin "1") (pinfunction "GND_1") (pintype "power_in"))
      (node (ref "J1") (pin "18") (pinfunction "VBATT-_18") (pintype "power_in"))
      (node (ref "JP2") (pin "1") (pinfunction "1_1") (pintype "passive"))
      (node (ref "R14") (pin "1") (pinfunction "1_1") (pintype "passive"))
      (node (ref "R15") (pin "1") (pinfunction "1_1") (pintype "passive"))
      (node (ref "R16") (pin "1") (pinfunction "1_1") (pintype "passive"))
      (node (ref "R17") (pin "1") (pinfunction "1_1") (pintype "passive"))
      (node (ref "R18") (pin "1") (pinfunction "1_1") (pintype "passive"))
      (node (ref "TP4") (pin "TESTPOINT") (pinfunction "TESTPOINT_TESTPOINT") (pintype "bidirectional"))
      (node (ref "U1") (pin "15") (pinfunction "PGND_15") (pintype "bidirectional"))
      (node (ref "U1") (pin "16") (pinfunction "PGND_16") (pintype "bidirectional"))
      (node (ref "U1") (pin "6") (pinfunction "AGND_6") (pintype "bidirectional"))
      (node (ref "U1") (pin "7") (pinfunction "FSW_7") (pintype "bidirectional"))
      (node (ref "U1") (pin "8") (pinfunction "DEF_8") (pintype "bidirectional"))
      (node (ref "U1") (pin "GND") (pinfunction "PGND_GND") (pintype "bidirectional"))
      (node (ref "U10") (pin "2") (pinfunction "GND_2") (pintype "open_collector"))
      (node (ref "U11") (pin "2") (pinfunction "GND_2") (pintype "open_collector"))
      (node (ref "U12") (pin "2") (pinfunction "GND_2") (pintype "open_collector"))
      (node (ref "U13") (pin "2") (pinfunction "GND_2") (pintype "open_collector"))
      (node (ref "U14") (pin "2") (pinfunction "GND_2") (pintype "open_collector"))
      (node (ref "U15") (pin "2") (pinfunction "GND_2") (pintype "open_collector"))
      (node (ref "U2") (pin "15") (pinfunction "PGND_15") (pintype "bidirectional"))
      (node (ref "U2") (pin "16") (pinfunction "PGND_16") (pintype "bidirectional"))
      (node (ref "U2") (pin "6") (pinfunction "AGND_6") (pintype "bidirectional"))
      (node (ref "U2") (pin "7") (pinfunction "FSW_7") (pintype "bidirectional"))
      (node (ref "U2") (pin "8") (pinfunction "DEF_8") (pintype "bidirectional"))
      (node (ref "U2") (pin "GND") (pinfunction "PGND_GND") (pintype "bidirectional"))
      (node (ref "U3") (pin "15") (pinfunction "PGND_15") (pintype "bidirectional"))
      (node (ref "U3") (pin "16") (pinfunction "PGND_16") (pintype "bidirectional"))
      (node (ref "U3") (pin "6") (pinfunction "AGND_6") (pintype "bidirectional"))
      (node (ref "U3") (pin "7") (pinfunction "FSW_7") (pintype "bidirectional"))
      (node (ref "U3") (pin "8") (pinfunction "DEF_8") (pintype "bidirectional"))
      (node (ref "U3") (pin "GND") (pinfunction "PGND_GND") (pintype "bidirectional"))
      (node (ref "U4") (pin "15") (pinfunction "PGND_15") (pintype "bidirectional"))
      (node (ref "U4") (pin "16") (pinfunction "PGND_16") (pintype "bidirectional"))
      (node (ref "U4") (pin "6") (pinfunction "AGND_6") (pintype "bidirectional"))
      (node (ref "U4") (pin "7") (pinfunction "FSW_7") (pintype "bidirectional"))
      (node (ref "U4") (pin "8") (pinfunction "DEF_8") (pintype "bidirectional"))
      (node (ref "U4") (pin "GND") (pinfunction "PGND_GND") (pintype "bidirectional"))
      (node (ref "U5") (pin "15") (pinfunction "PGND_15") (pintype "bidirectional"))
      (node (ref "U5") (pin "16") (pinfunction "PGND_16") (pintype "bidirectional"))
      (node (ref "U5") (pin "6") (pinfunction "AGND_6") (pintype "bidirectional"))
      (node (ref "U5") (pin "7") (pinfunction "FSW_7") (pintype "bidirectional"))
      (node (ref "U5") (pin "8") (pinfunction "DEF_8") (pintype "bidirectional"))
      (node (ref "U5") (pin "GND") (pinfunction "PGND_GND") (pintype "bidirectional"))
      (node (ref "U6") (pin "1") (pinfunction "A0_1") (pintype "bidirectional"))
      (node (ref "U6") (pin "10") (pinfunction "GND_10") (pintype "bidirectional"))
      (node (ref "U6") (pin "2") (pinfunction "A1_2") (pintype "bidirectional"))
      (node (ref "U6") (pin "3") (pinfunction "A2_3") (pintype "bidirectional"))
      (node (ref "U7") (pin "10") (pinfunction "GND_10") (pintype "bidirectional"))
      (node (ref "U7") (pin "2") (pinfunction "A1_2") (pintype "bidirectional"))
      (node (ref "U7") (pin "3") (pinfunction "A2_3") (pintype "bidirectional"))
      (node (ref "U8") (pin "2") (pinfunction "GND_2") (pintype "open_collector"))
      (node (ref "U9") (pin "2") (pinfunction "GND_2") (pintype "open_collector"))
    )
    (net (code "7") (name "Net-(L1-1)") (class "Default")
      (node (ref "L1") (pin "P$1") (pinfunction "1_P$1") (pintype "bidirectional"))
      (node (ref "U1") (pin "1") (pinfunction "SW_1") (pintype "bidirectional"))
      (node (ref "U1") (pin "2") (pinfunction "SW_2") (pintype "bidirectional"))
      (node (ref "U1") (pin "3") (pinfunction "SW_3") (pintype "bidirectional"))
    )
    (net (code "8") (name "Net-(L2-1)") (class "Default")
      (node (ref "L2") (pin "P$1") (pinfunction "1_P$1") (pintype "bidirectional"))
      (node (ref "U2") (pin "1") (pinfunction "SW_1") (pintype "bidirectional"))
      (node (ref "U2") (pin "2") (pinfunction "SW_2") (pintype "bidirectional"))
      (node (ref "U2") (pin "3") (pinfunction "SW_3") (pintype "bidirectional"))
    )
    (net (code "9") (name "Net-(L3-1)") (class "Default")
      (node (ref "L3") (pin "P$1") (pinfunction "1_P$1") (pintype "bidirectional"))
      (node (ref "U3") (pin "1") (pinfunction "SW_1") (pintype "bidirectional"))
      (node (ref "U3") (pin "2") (pinfunction "SW_2") (pintype "bidirectional"))
      (node (ref "U3") (pin "3") (pinfunction "SW_3") (pintype "bidirectional"))
    )
    (net (code "10") (name "Net-(L4-1)") (class "Default")
      (node (ref "L4") (pin "P$1") (pinfunction "1_P$1") (pintype "bidirectional"))
      (node (ref "U4") (pin "1") (pinfunction "SW_1") (pintype "bidirectional"))
      (node (ref "U4") (pin "2") (pinfunction "SW_2") (pintype "bidirectional"))
      (node (ref "U4") (pin "3") (pinfunction "SW_3") (pintype "bidirectional"))
    )
    (net (code "11") (name "Net-(L5-1)") (class "Default")
      (node (ref "L5") (pin "P$1") (pinfunction "1_P$1") (pintype "bidirectional"))
      (node (ref "U5") (pin "1") (pinfunction "SW_1") (pintype "bidirectional"))
      (node (ref "U5") (pin "2") (pinfunction "SW_2") (pintype "bidirectional"))
      (node (ref "U5") (pin "3") (pinfunction "SW_3") (pintype "bidirectional"))
    )
    (net (code "12") (name "Net-(U1-FB)") (class "Default")
      (node (ref "R18") (pin "2") (pinfunction "2_2") (pintype "passive"))
      (node (ref "R23") (pin "1") (pinfunction "1_1") (pintype "passive"))
      (node (ref "U1") (pin "5") (pinfunction "FB_5") (pintype "bidirectional"))
    )
    (net (code "13") (name "Net-(U1-PG)") (class "Default")
      (node (ref "R9") (pin "1") (pinfunction "1_1") (pintype "passive"))
      (node (ref "U1") (pin "4") (pinfunction "PG_4") (pintype "bidirectional"))
    )
    (net (code "14") (name "Net-(U1-SS{slash}TR)") (class "Default")
      (node (ref "C1") (pin "2") (pinfunction "2_2") (pintype "bidirectional"))
      (node (ref "U1") (pin "9") (pinfunction "SS/TR_9") (pintype "bidirectional"))
    )
    (net (code "15") (name "Net-(U2-FB)") (class "Default")
      (node (ref "R14") (pin "2") (pinfunction "2_2") (pintype "passive"))
      (node (ref "R19") (pin "1") (pinfunction "1_1") (pintype "passive"))
      (node (ref "U2") (pin "5") (pinfunction "FB_5") (pintype "bidirectional"))
    )
    (net (code "16") (name "Net-(U2-PG)") (class "Default")
      (node (ref "R10") (pin "1") (pinfunction "1_1") (pintype "passive"))
      (node (ref "U2") (pin "4") (pinfunction "PG_4") (pintype "bidirectional"))
    )
    (net (code "17") (name "Net-(U2-SS{slash}TR)") (class "Default")
      (node (ref "C2") (pin "2") (pinfunction "2_2") (pintype "bidirectional"))
      (node (ref "U2") (pin "9") (pinfunction "SS/TR_9") (pintype "bidirectional"))
    )
    (net (code "18") (name "Net-(U3-FB)") (class "Default")
      (node (ref "R15") (pin "2") (pinfunction "2_2") (pintype "passive"))
      (node (ref "R20") (pin "1") (pinfunction "1_1") (pintype "passive"))
      (node (ref "U3") (pin "5") (pinfunction "FB_5") (pintype "bidirectional"))
    )
    (net (code "19") (name "Net-(U3-PG)") (class "Default")
      (node (ref "R11") (pin "1") (pinfunction "1_1") (pintype "passive"))
      (node (ref "U3") (pin "4") (pinfunction "PG_4") (pintype "bidirectional"))
    )
    (net (code "20") (name "Net-(U3-SS{slash}TR)") (class "Default")
      (node (ref "C3") (pin "2") (pinfunction "2_2") (pintype "bidirectional"))
      (node (ref "U3") (pin "9") (pinfunction "SS/TR_9") (pintype "bidirectional"))
    )
    (net (code "21") (name "Net-(U4-FB)") (class "Default")
      (node (ref "R16") (pin "2") (pinfunction "2_2") (pintype "passive"))
      (node (ref "R21") (pin "1") (pinfunction "1_1") (pintype "passive"))
      (node (ref "U4") (pin "5") (pinfunction "FB_5") (pintype "bidirectional"))
    )
    (net (code "22") (name "Net-(U4-PG)") (class "Default")
      (node (ref "R12") (pin "1") (pinfunction "1_1") (pintype "passive"))
      (node (ref "U4") (pin "4") (pinfunction "PG_4") (pintype "bidirectional"))
    )
    (net (code "23") (name "Net-(U4-SS{slash}TR)") (class "Default")
      (node (ref "C4") (pin "2") (pinfunction "2_2") (pintype "bidirectional"))
      (node (ref "U4") (pin "9") (pinfunction "SS/TR_9") (pintype "bidirectional"))
    )
    (net (code "24") (name "Net-(U5-FB)") (class "Default")
      (node (ref "R17") (pin "2") (pinfunction "2_2") (pintype "passive"))
      (node (ref "R22") (pin "1") (pinfunction "1_1") (pintype "passive"))
      (node (ref "U5") (pin "5") (pinfunction "FB_5") (pintype "bidirectional"))
    )
    (net (code "25") (name "Net-(U5-PG)") (class "Default")
      (node (ref "R13") (pin "1") (pinfunction "1_1") (pintype "passive"))
      (node (ref "U5") (pin "4") (pinfunction "PG_4") (pintype "bidirectional"))
    )
    (net (code "26") (name "Net-(U5-SS{slash}TR)") (class "Default")
      (node (ref "C5") (pin "2") (pinfunction "2_2") (pintype "bidirectional"))
      (node (ref "U5") (pin "9") (pinfunction "SS/TR_9") (pintype "bidirectional"))
    )
    (net (code "27") (name "Net-(U6-SC0)") (class "Default")
      (node (ref "U6") (pin "6") (pinfunction "SC0_6") (pintype "bidirectional"))
      (node (ref "U8") (pin "3") (pinfunction "SCL_3") (pintype "open_collector"))
    )
    (net (code "28") (name "Net-(U6-SC1)") (class "Default")
      (node (ref "U6") (pin "9") (pinfunction "SC1_9") (pintype "bidirectional"))
      (node (ref "U9") (pin "3") (pinfunction "SCL_3") (pintype "open_collector"))
    )
    (net (code "29") (name "Net-(U6-SD0)") (class "Default")
      (node (ref "U6") (pin "5") (pinfunction "SD0_5") (pintype "bidirectional"))
      (node (ref "U8") (pin "4") (pinfunction "SDA_4") (pintype "open_collector"))
    )
    (net (code "30") (name "Net-(U6-SD1)") (class "Default")
      (node (ref "U6") (pin "8") (pinfunction "SD1_8") (pintype "bidirectional"))
      (node (ref "U9") (pin "4") (pinfunction "SDA_4") (pintype "open_collector"))
    )
    (net (code "31") (name "Net-(U6-~{INT0})") (class "Default")
      (node (ref "U6") (pin "4") (pinfunction "~{INT0}_4") (pintype "bidirectional"))
      (node (ref "U8") (pin "5") (pinfunction "~{ALERT}_5") (pintype "open_collector"))
    )
    (net (code "32") (name "Net-(U6-~{INT1})") (class "Default")
      (node (ref "U6") (pin "7") (pinfunction "~{INT1}_7") (pintype "bidirectional"))
      (node (ref "U9") (pin "5") (pinfunction "~{ALERT}_5") (pintype "open_collector"))
    )
    (net (code "33") (name "Net-(U10-SCL)") (class "Default")
      (node (ref "U10") (pin "3") (pinfunction "SCL_3") (pintype "open_collector"))
      (node (ref "U6") (pin "13") (pinfunction "SC2_13") (pintype "bidirectional"))
    )
    (net (code "34") (name "Net-(U10-SDA)") (class "Default")
      (node (ref "U10") (pin "4") (pinfunction "SDA_4") (pintype "open_collector"))
      (node (ref "U6") (pin "12") (pinfunction "SD2_12") (pintype "bidirectional"))
    )
    (net (code "35") (name "Net-(U10-~{ALERT})") (class "Default")
      (node (ref "U10") (pin "5") (pinfunction "~{ALERT}_5") (pintype "open_collector"))
      (node (ref "U6") (pin "11") (pinfunction "~{INT2}_11") (pintype "bidirectional"))
    )
    (net (code "36") (name "Net-(U11-SCL)") (class "Default")
      (node (ref "U11") (pin "3") (pinfunction "SCL_3") (pintype "open_collector"))
      (node (ref "U6") (pin "16") (pinfunction "SC3_16") (pintype "bidirectional"))
    )
    (net (code "37") (name "Net-(U11-SDA)") (class "Default")
      (node (ref "U11") (pin "4") (pinfunction "SDA_4") (pintype "open_collector"))
      (node (ref "U6") (pin "15") (pinfunction "SD3_15") (pintype "bidirectional"))
    )
    (net (code "38") (name "Net-(U11-~{ALERT})") (class "Default")
      (node (ref "U11") (pin "5") (pinfunction "~{ALERT}_5") (pintype "open_collector"))
      (node (ref "U6") (pin "14") (pinfunction "~{INT3}_14") (pintype "bidirectional"))
    )
    (net (code "39") (name "Net-(U12-SCL)") (class "Default")
      (node (ref "U12") (pin "3") (pinfunction "SCL_3") (pintype "open_collector"))
      (node (ref "U7") (pin "6") (pinfunction "SC0_6") (pintype "bidirectional"))
    )
    (net (code "40") (name "Net-(U12-SDA)") (class "Default")
      (node (ref "U12") (pin "4") (pinfunction "SDA_4") (pintype "open_collector"))
      (node (ref "U7") (pin "5") (pinfunction "SD0_5") (pintype "bidirectional"))
    )
    (net (code "41") (name "Net-(U12-~{ALERT})") (class "Default")
      (node (ref "U12") (pin "5") (pinfunction "~{ALERT}_5") (pintype "open_collector"))
      (node (ref "U7") (pin "4") (pinfunction "~{INT0}_4") (pintype "bidirectional"))
    )
    (net (code "42") (name "Net-(U13-SCL)") (class "Default")
      (node (ref "U13") (pin "3") (pinfunction "SCL_3") (pintype "open_collector"))
      (node (ref "U7") (pin "9") (pinfunction "SC1_9") (pintype "bidirectional"))
    )
    (net (code "43") (name "Net-(U13-SDA)") (class "Default")
      (node (ref "U13") (pin "4") (pinfunction "SDA_4") (pintype "open_collector"))
      (node (ref "U7") (pin "8") (pinfunction "SD1_8") (pintype "bidirectional"))
    )
    (net (code "44") (name "Net-(U13-~{ALERT})") (class "Default")
      (node (ref "U13") (pin "5") (pinfunction "~{ALERT}_5") (pintype "open_collector"))
      (node (ref "U7") (pin "7") (pinfunction "~{INT1}_7") (pintype "bidirectional"))
    )
    (net (code "45") (name "Net-(U14-SCL)") (class "Default")
      (node (ref "U14") (pin "3") (pinfunction "SCL_3") (pintype "open_collector"))
      (node (ref "U7") (pin "13") (pinfunction "SC2_13") (pintype "bidirectional"))
    )
    (net (code "46") (name "Net-(U14-SDA)") (class "Default")
      (node (ref "U14") (pin "4") (pinfunction "SDA_4") (pintype "open_collector"))
      (node (ref "U7") (pin "12") (pinfunction "SD2_12") (pintype "bidirectional"))
    )
    (net (code "47") (name "Net-(U14-~{ALERT})") (class "Default")
      (node (ref "U14") (pin "5") (pinfunction "~{ALERT}_5") (pintype "open_collector"))
      (node (ref "U7") (pin "11") (pinfunction "~{INT2}_11") (pintype "bidirectional"))
    )
    (net (code "48") (name "Net-(U15-SCL)") (class "Default")
      (node (ref "U15") (pin "3") (pinfunction "SCL_3") (pintype "open_collector"))
      (node (ref "U7") (pin "16") (pinfunction "SC3_16") (pintype "bidirectional"))
    )
    (net (code "49") (name "Net-(U15-SDA)") (class "Default")
      (node (ref "U15") (pin "4") (pinfunction "SDA_4") (pintype "open_collector"))
      (node (ref "U7") (pin "15") (pinfunction "SD3_15") (pintype "bidirectional"))
    )
    (net (code "50") (name "Net-(U15-~{ALERT})") (class "Default")
      (node (ref "U15") (pin "5") (pinfunction "~{ALERT}_5") (pintype "open_collector"))
      (node (ref "U7") (pin "14") (pinfunction "~{INT3}_14") (pintype "bidirectional"))
    )
    (net (code "51") (name "SCL") (class "Default")
      (node (ref "J1") (pin "5") (pinfunction "SMBCLK_5") (pintype "open_collector"))
      (node (ref "TP19") (pin "TESTPOINT") (pinfunction "TESTPOINT_TESTPOINT") (pintype "bidirectional"))
      (node (ref "U6") (pin "18") (pinfunction "SCL_18") (pintype "bidirectional"))
      (node (ref "U7") (pin "18") (pinfunction "SCL_18") (pintype "bidirectional"))
    )
    (net (code "52") (name "SDA") (class "Default")
      (node (ref "J1") (pin "3") (pinfunction "SMBDATA_3") (pintype "open_collector"))
      (node (ref "TP18") (pin "TESTPOINT") (pinfunction "TESTPOINT_TESTPOINT") (pintype "bidirectional"))
      (node (ref "U6") (pin "19") (pinfunction "SDA_19") (pintype "bidirectional"))
      (node (ref "U7") (pin "19") (pinfunction "SDA_19") (pintype "bidirectional"))
    )
    (net (code "53") (name "VBATT") (class "Default")
      (node (ref "C10") (pin "1") (pinfunction "1_1") (pintype "bidirectional"))
      (node (ref "C19") (pin "P$1") (pinfunction "1_P$1") (pintype "bidirectional"))
      (node (ref "C20") (pin "P$1") (pinfunction "1_P$1") (pintype "bidirectional"))
      (node (ref "C21") (pin "P$1") (pinfunction "1_P$1") (pintype "bidirectional"))
      (node (ref "C22") (pin "P$1") (pinfunction "1_P$1") (pintype "bidirectional"))
      (node (ref "C23") (pin "P$1") (pinfunction "1_P$1") (pintype "bidirectional"))
      (node (ref "C6") (pin "1") (pinfunction "1_1") (pintype "bidirectional"))
      (node (ref "C7") (pin "1") (pinfunction "1_1") (pintype "bidirectional"))
      (node (ref "C8") (pin "1") (pinfunction "1_1") (pintype "bidirectional"))
      (node (ref "C9") (pin "1") (pinfunction "1_1") (pintype "bidirectional"))
      (node (ref "J1") (pin "17") (pinfunction "VBATT+_17") (pintype "power_in"))
      (node (ref "JP2") (pin "2") (pinfunction "2_2") (pintype "passive"))
      (node (ref "TP3") (pin "TESTPOINT") (pinfunction "TESTPOINT_TESTPOINT") (pintype "bidirectional"))
      (node (ref "U1") (pin "10") (pinfunction "AVIN_10") (pintype "bidirectional"))
      (node (ref "U1") (pin "11") (pinfunction "PVIN_11") (pintype "bidirectional"))
      (node (ref "U1") (pin "12") (pinfunction "PVIN_12") (pintype "bidirectional"))
      (node (ref "U1") (pin "13") (pinfunction "EN_13") (pintype "bidirectional"))
      (node (ref "U2") (pin "10") (pinfunction "AVIN_10") (pintype "bidirectional"))
      (node (ref "U2") (pin "11") (pinfunction "PVIN_11") (pintype "bidirectional"))
      (node (ref "U2") (pin "12") (pinfunction "PVIN_12") (pintype "bidirectional"))
      (node (ref "U2") (pin "13") (pinfunction "EN_13") (pintype "bidirectional"))
      (node (ref "U3") (pin "10") (pinfunction "AVIN_10") (pintype "bidirectional"))
      (node (ref "U3") (pin "11") (pinfunction "PVIN_11") (pintype "bidirectional"))
      (node (ref "U3") (pin "12") (pinfunction "PVIN_12") (pintype "bidirectional"))
      (node (ref "U3") (pin "13") (pinfunction "EN_13") (pintype "bidirectional"))
      (node (ref "U4") (pin "10") (pinfunction "AVIN_10") (pintype "bidirectional"))
      (node (ref "U4") (pin "11") (pinfunction "PVIN_11") (pintype "bidirectional"))
      (node (ref "U4") (pin "12") (pinfunction "PVIN_12") (pintype "bidirectional"))
      (node (ref "U4") (pin "13") (pinfunction "EN_13") (pintype "bidirectional"))
      (node (ref "U5") (pin "10") (pinfunction "AVIN_10") (pintype "bidirectional"))
      (node (ref "U5") (pin "11") (pinfunction "PVIN_11") (pintype "bidirectional"))
      (node (ref "U5") (pin "12") (pinfunction "PVIN_12") (pintype "bidirectional"))
      (node (ref "U5") (pin "13") (pinfunction "EN_13") (pintype "bidirectional"))
    )
    (net (code "54") (name "VCC_BACKPLANE") (class "Default")
      (node (ref "C11") (pin "1") (pinfunction "1_1") (pintype "bidirectional"))
      (node (ref "J1") (pin "13") (pinfunction "VCC_BACKPLANE_13") (pintype "power_in"))
      (node (ref "J1") (pin "2") (pinfunction "VCC_CONTROLLER_2") (pintype "power_in"))
      (node (ref "R1") (pin "1") (pinfunction "1_1") (pintype "passive"))
      (node (ref "TP11") (pin "TESTPOINT") (pinfunction "TESTPOINT_TESTPOINT") (pintype "bidirectional"))
      (node (ref "U6") (pin "20") (pinfunction "VCC_20") (pintype "bidirectional"))
      (node (ref "U7") (pin "1") (pinfunction "A0_1") (pintype "bidirectional"))
      (node (ref "U7") (pin "20") (pinfunction "VCC_20") (pintype "bidirectional"))
      (node (ref "U8") (pin "6") (pinfunction "SENSE-_6") (pintype "open_collector"))
    )
    (net (code "55") (name "VCC_LINUX") (class "Default")
      (node (ref "C12") (pin "1") (pinfunction "1_1") (pintype "bidirectional"))
      (node (ref "J1") (pin "4") (pinfunction "VCC_LINUX_4") (pintype "power_in"))
      (node (ref "R2") (pin "1") (pinfunction "1_1") (pintype "passive"))
      (node (ref "TP10") (pin "TESTPOINT") (pinfunction "TESTPOINT_TESTPOINT") (pintype "bidirectional"))
      (node (ref "U9") (pin "6") (pinfunction "SENSE-_6") (pintype "open_collector"))
    )
    (net (code "56") (name "VCC_MOD0") (class "Default")
      (node (ref "C13") (pin "1") (pinfunction "1_1") (pintype "bidirectional"))
      (node (ref "J1") (pin "7") (pinfunction "VCC_MOD0_7") (pintype "power_in"))
      (node (ref "R3") (pin "1") (pinfunction "1_1") (pintype "passive"))
      (node (ref "TP12") (pin "TESTPOINT") (pinfunction "TESTPOINT_TESTPOINT") (pintype "bidirectional"))
      (node (ref "U10") (pin "6") (pinfunction "SENSE-_6") (pintype "open_collector"))
    )
    (net (code "57") (name "VCC_MOD1") (class "Default")
      (node (ref "C14") (pin "1") (pinfunction "1_1") (pintype "bidirectional"))
      (node (ref "J1") (pin "8") (pinfunction "VCC_MOD1_8") (pintype "power_in"))
      (node (ref "R4") (pin "1") (pinfunction "1_1") (pintype "passive"))
      (node (ref "TP13") (pin "TESTPOINT") (pinfunction "TESTPOINT_TESTPOINT") (pintype "bidirectional"))
      (node (ref "U11") (pin "6") (pinfunction "SENSE-_6") (pintype "open_collector"))
    )
    (net (code "58") (name "VCC_MOD2") (class "Default")
      (node (ref "C15") (pin "1") (pinfunction "1_1") (pintype "bidirectional"))
      (node (ref "J1") (pin "9") (pinfunction "VCC_MOD2_9") (pintype "power_in"))
      (node (ref "R5") (pin "1") (pinfunction "1_1") (pintype "passive"))
      (node (ref "TP14") (pin "TESTPOINT") (pinfunction "TESTPOINT_TESTPOINT") (pintype "bidirectional"))
      (node (ref "U12") (pin "6") (pinfunction "SENSE-_6") (pintype "open_collector"))
    )
    (net (code "59") (name "VCC_MOD5") (class "Default")
      (node (ref "C16") (pin "1") (pinfunction "1_1") (pintype "bidirectional"))
      (node (ref "J1") (pin "10") (pinfunction "VCC_MOD5_10") (pintype "power_in"))
      (node (ref "R6") (pin "1") (pinfunction "1_1") (pintype "passive"))
      (node (ref "TP15") (pin "TESTPOINT") (pinfunction "TESTPOINT_TESTPOINT") (pintype "bidirectional"))
      (node (ref "U13") (pin "6") (pinfunction "SENSE-_6") (pintype "open_collector"))
    )
    (net (code "60") (name "VCC_MOD6") (class "Default")
      (node (ref "C17") (pin "1") (pinfunction "1_1") (pintype "bidirectional"))
      (node (ref "J1") (pin "11") (pinfunction "VCC_MOD6_11") (pintype "power_in"))
      (node (ref "R7") (pin "1") (pinfunction "1_1") (pintype "passive"))
      (node (ref "TP16") (pin "TESTPOINT") (pinfunction "TESTPOINT_TESTPOINT") (pintype "bidirectional"))
      (node (ref "U14") (pin "6") (pinfunction "SENSE-_6") (pintype "open_collector"))
    )
    (net (code "61") (name "VCC_MOD7") (class "Default")
      (node (ref "C18") (pin "1") (pinfunction "1_1") (pintype "bidirectional"))
      (node (ref "J1") (pin "12") (pinfunction "VCC_MOD7_12") (pintype "power_in"))
      (node (ref "R8") (pin "1") (pinfunction "1_1") (pintype "passive"))
      (node (ref "TP17") (pin "TESTPOINT") (pinfunction "TESTPOINT_TESTPOINT") (pintype "bidirectional"))
      (node (ref "U15") (pin "6") (pinfunction "SENSE-_6") (pintype "open_collector"))
    )
    (net (code "62") (name "VSOL+") (class "Default")
      (node (ref "J1") (pin "19") (pinfunction "VSOL+_19") (pintype "power_in"))
      (node (ref "JP1") (pin "2") (pinfunction "2_2") (pintype "passive"))
      (node (ref "TP1") (pin "TESTPOINT") (pinfunction "TESTPOINT_TESTPOINT") (pintype "bidirectional"))
    )
    (net (code "63") (name "VSOL-") (class "Default")
      (node (ref "J1") (pin "20") (pinfunction "VSOL-_20") (pintype "power_in"))
      (node (ref "JP1") (pin "1") (pinfunction "1_1") (pintype "passive"))
      (node (ref "TP2") (pin "TESTPOINT") (pinfunction "TESTPOINT_TESTPOINT") (pintype "bidirectional"))
    )
    (net (code "64") (name "~{INT}") (class "Default")
      (node (ref "J1") (pin "6") (pinfunction "~{SMBALERT}_6") (pintype "bidirectional"))
      (node (ref "TP20") (pin "TESTPOINT") (pinfunction "TESTPOINT_TESTPOINT") (pintype "bidirectional"))
      (node (ref "U6") (pin "17") (pinfunction "~{INT}_17") (pintype "bidirectional"))
      (node (ref "U7") (pin "17") (pinfunction "~{INT}_17") (pintype "bidirectional"))
    )
  )
)
